# SCH_2022-03-13.net
KiCad netlist of a schematic drawn in Altium Designer
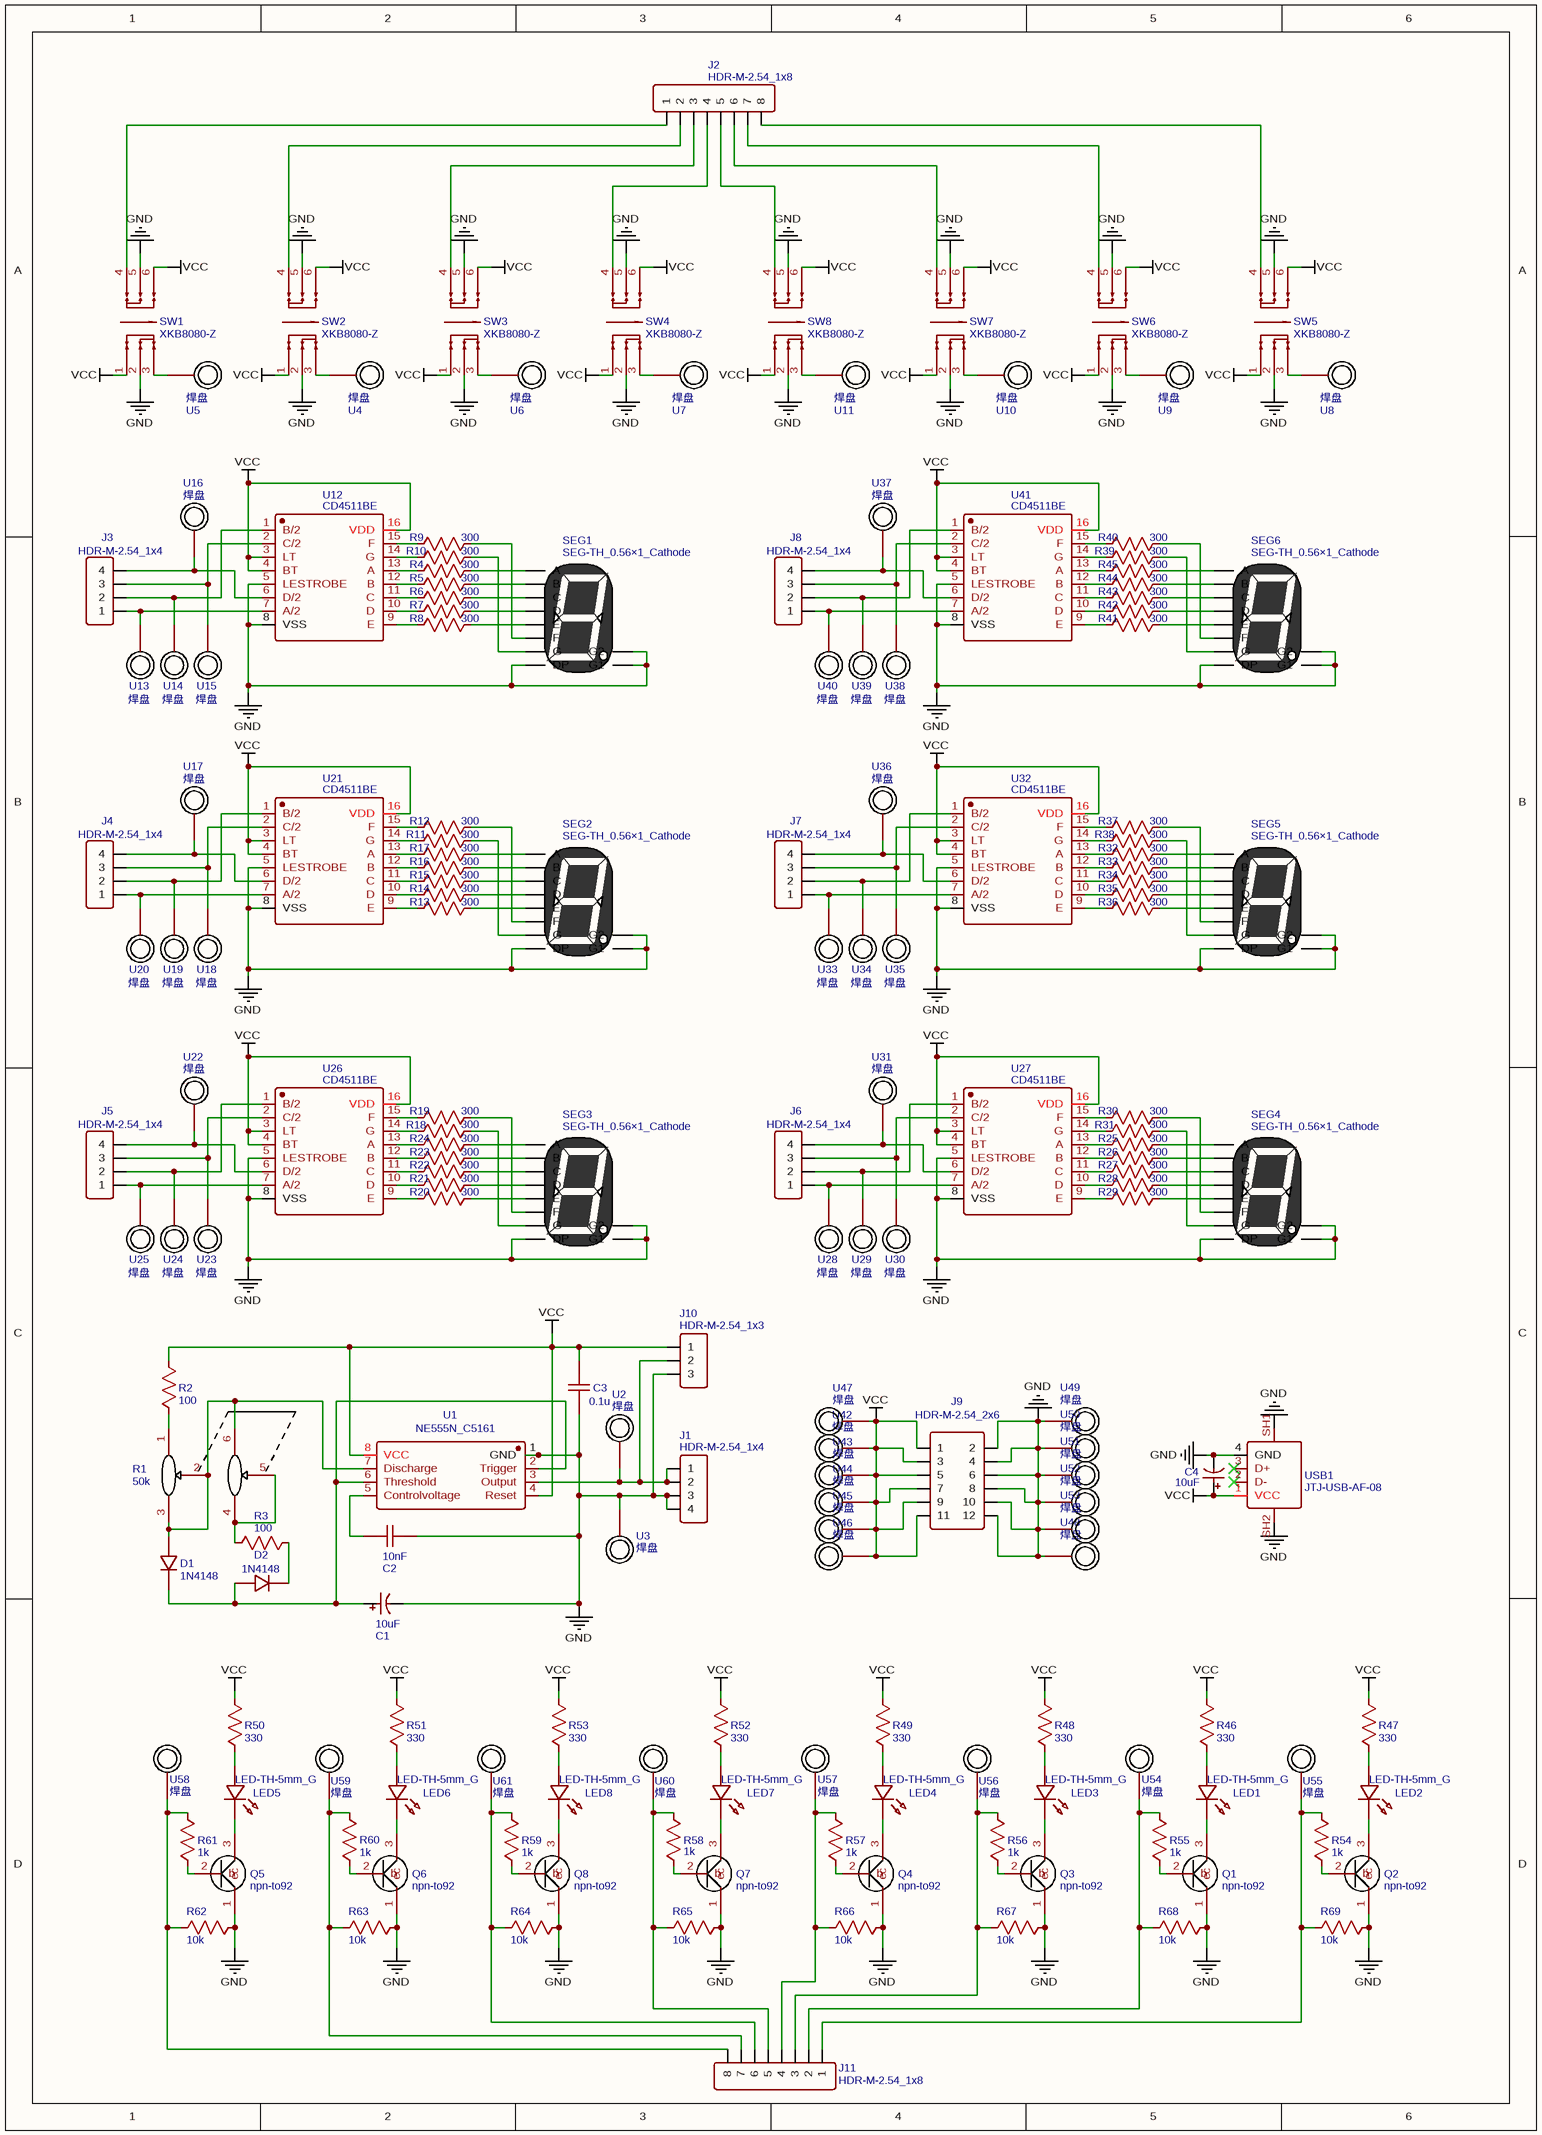
[diagram p0: SCH_2022-03-13.schdoc]

(export (version "E")
  (design (tool "Eeschema 10.0.6"))
  (components
    (comp (ref "C1")
      (value "10uF")
      (footprint "CAP-TH_BD1.0-P2.54-D6.3-FD")
      (fields
        (field (name "BOM_SUPPLIER PART") "C45076")
        (field (name "BOM_MANUFACTURER PART") "100uF 35V 6.3*11")
      )
      (libsource (lib "altium-import") (part "root_0_10uF_"))
    )
    (comp (ref "C2")
      (value "10nF")
      (footprint "RAD-0.2")
      (fields (field (name "CONTRIBUTOR") "LCEDA_Lib"))
      (libsource (lib "altium-import") (part "root_2_10nF_"))
    )
    (comp (ref "C3")
      (value "0.1u")
      (footprint "RAD-0.2")
      (fields (field (name "CONTRIBUTOR") "LCEDA_Lib"))
      (libsource (lib "altium-import") (part "root_1_0.1u_"))
    )
    (comp (ref "C4")
      (value "10uF")
      (footprint "CAP-TH_BD1.0-P2.54-D6.3-FD")
      (fields
        (field (name "BOM_SUPPLIER PART") "C45076")
        (field (name "BOM_MANUFACTURER PART") "100uF 35V 6.3*11")
      )
      (libsource (lib "altium-import") (part "root_1_10uF_"))
    )
    (comp (ref "D1")
      (value "1N4148")
      (footprint "DO-35_BD2.0-L4.2-P8.20-D0.5-RD")
      (fields (field (name "BOM_SUPPLIER PART") "C13769") (field (name "CONTRIBUTOR") "LCSC"))
      (libsource (lib "altium-import") (part "root_1_1N4148_"))
    )
    (comp (ref "D2")
      (value "1N4148")
      (footprint "DO-35_BD2.0-L4.2-P8.20-D0.5-RD")
      (fields (field (name "BOM_SUPPLIER PART") "C13769") (field (name "CONTRIBUTOR") "LCSC"))
      (libsource (lib "altium-import") (part "root_2_1N4148_"))
    )
    (comp (ref "J1")
      (value "HDR-M-2.54_1x4")
      (footprint "HDR-M-2.54_1X4")
      (fields (field (name "BOM_SUPPLIER PART") "C124378") (field (name "CONTRIBUTOR") "LCEDA_Lib"))
      (libsource (lib "altium-import") (part "root_0_HDR-M-2.54_1x4_"))
    )
    (comp (ref "J2")
      (value "HDR-M-2.54_1x8")
      (footprint "HDR-M-2.54_1X8")
      (fields (field (name "BOM_SUPPLIER PART") "C190820") (field (name "CONTRIBUTOR") "LCEDA_Lib"))
      (libsource (lib "altium-import") (part "root_1_HDR-M-2.54_1x8_"))
    )
    (comp (ref "J3")
      (value "HDR-M-2.54_1x4")
      (footprint "HDR-M-2.54_1X4")
      (fields (field (name "BOM_SUPPLIER PART") "C124378") (field (name "CONTRIBUTOR") "LCEDA_Lib"))
      (libsource (lib "altium-import") (part "root_2_HDR-M-2.54_1x4_"))
    )
    (comp (ref "J4")
      (value "HDR-M-2.54_1x4")
      (footprint "HDR-M-2.54_1X4")
      (fields (field (name "BOM_SUPPLIER PART") "C124378") (field (name "CONTRIBUTOR") "LCEDA_Lib"))
      (libsource (lib "altium-import") (part "root_2_HDR-M-2.54_1x4_"))
    )
    (comp (ref "J5")
      (value "HDR-M-2.54_1x4")
      (footprint "HDR-M-2.54_1X4")
      (fields (field (name "BOM_SUPPLIER PART") "C124378") (field (name "CONTRIBUTOR") "LCEDA_Lib"))
      (libsource (lib "altium-import") (part "root_2_HDR-M-2.54_1x4_"))
    )
    (comp (ref "J6")
      (value "HDR-M-2.54_1x4")
      (footprint "HDR-M-2.54_1X4")
      (fields (field (name "BOM_SUPPLIER PART") "C124378") (field (name "CONTRIBUTOR") "LCEDA_Lib"))
      (libsource (lib "altium-import") (part "root_2_HDR-M-2.54_1x4_"))
    )
    (comp (ref "J7")
      (value "HDR-M-2.54_1x4")
      (footprint "HDR-M-2.54_1X4")
      (fields (field (name "BOM_SUPPLIER PART") "C124378") (field (name "CONTRIBUTOR") "LCEDA_Lib"))
      (libsource (lib "altium-import") (part "root_2_HDR-M-2.54_1x4_"))
    )
    (comp (ref "J8")
      (value "HDR-M-2.54_1x4")
      (footprint "HDR-M-2.54_1X4")
      (fields (field (name "BOM_SUPPLIER PART") "C124378") (field (name "CONTRIBUTOR") "LCEDA_Lib"))
      (libsource (lib "altium-import") (part "root_2_HDR-M-2.54_1x4_"))
    )
    (comp (ref "J9")
      (value "HDR-M-2.54_2x6")
      (footprint "HDR-M-2.54_2X6")
      (fields (field (name "BOM_SUPPLIER PART") "C124388") (field (name "CONTRIBUTOR") "LCEDA_Lib"))
      (libsource (lib "altium-import") (part "root_0_HDR-M-2.54_2x6_"))
    )
    (comp (ref "J10")
      (value "HDR-M-2.54_1x3")
      (footprint "HDR-M-2.54_1X3")
      (fields (field (name "BOM_SUPPLIER PART") "C180248") (field (name "CONTRIBUTOR") "LCEDA_Lib"))
      (libsource (lib "altium-import") (part "root_0_HDR-M-2.54_1x3_"))
    )
    (comp (ref "J11")
      (value "HDR-M-2.54_1x8")
      (footprint "HDR-M-2.54_1X8")
      (fields (field (name "BOM_SUPPLIER PART") "C190820") (field (name "CONTRIBUTOR") "LCEDA_Lib"))
      (libsource (lib "altium-import") (part "root_3_HDR-M-2.54_1x8_"))
    )
    (comp (ref "LED1")
      (value "LED-TH-5mm_G")
      (footprint "LED-TH_BD5.0_GREEN")
      (fields
        (field (name "BOM_MANUFACTURER PART") "333-2SYGD/S530-E2")
        (field (name "BOM_SUPPLIER PART") "C88163")
        (field (name "CONTRIBUTOR") "LCEDA_Lib")
      )
      (libsource (lib "altium-import") (part "root_3_LED-TH-5mm_G_"))
    )
    (comp (ref "LED2")
      (value "LED-TH-5mm_G")
      (footprint "LED-TH_BD5.0_GREEN")
      (fields
        (field (name "BOM_MANUFACTURER PART") "333-2SYGD/S530-E2")
        (field (name "BOM_SUPPLIER PART") "C88163")
        (field (name "CONTRIBUTOR") "LCEDA_Lib")
      )
      (libsource (lib "altium-import") (part "root_3_LED-TH-5mm_G_"))
    )
    (comp (ref "LED3")
      (value "LED-TH-5mm_G")
      (footprint "LED-TH_BD5.0_GREEN")
      (fields
        (field (name "BOM_MANUFACTURER PART") "333-2SYGD/S530-E2")
        (field (name "BOM_SUPPLIER PART") "C88163")
        (field (name "CONTRIBUTOR") "LCEDA_Lib")
      )
      (libsource (lib "altium-import") (part "root_3_LED-TH-5mm_G_"))
    )
    (comp (ref "LED4")
      (value "LED-TH-5mm_G")
      (footprint "LED-TH_BD5.0_GREEN")
      (fields
        (field (name "BOM_MANUFACTURER PART") "333-2SYGD/S530-E2")
        (field (name "BOM_SUPPLIER PART") "C88163")
        (field (name "CONTRIBUTOR") "LCEDA_Lib")
      )
      (libsource (lib "altium-import") (part "root_3_LED-TH-5mm_G_"))
    )
    (comp (ref "LED5")
      (value "LED-TH-5mm_G")
      (footprint "LED-TH_BD5.0_GREEN")
      (fields
        (field (name "BOM_MANUFACTURER PART") "333-2SYGD/S530-E2")
        (field (name "BOM_SUPPLIER PART") "C88163")
        (field (name "CONTRIBUTOR") "LCEDA_Lib")
      )
      (libsource (lib "altium-import") (part "root_3_LED-TH-5mm_G_"))
    )
    (comp (ref "LED6")
      (value "LED-TH-5mm_G")
      (footprint "LED-TH_BD5.0_GREEN")
      (fields
        (field (name "BOM_MANUFACTURER PART") "333-2SYGD/S530-E2")
        (field (name "BOM_SUPPLIER PART") "C88163")
        (field (name "CONTRIBUTOR") "LCEDA_Lib")
      )
      (libsource (lib "altium-import") (part "root_3_LED-TH-5mm_G_"))
    )
    (comp (ref "LED7")
      (value "LED-TH-5mm_G")
      (footprint "LED-TH_BD5.0_GREEN")
      (fields
        (field (name "BOM_MANUFACTURER PART") "333-2SYGD/S530-E2")
        (field (name "BOM_SUPPLIER PART") "C88163")
        (field (name "CONTRIBUTOR") "LCEDA_Lib")
      )
      (libsource (lib "altium-import") (part "root_3_LED-TH-5mm_G_"))
    )
    (comp (ref "LED8")
      (value "LED-TH-5mm_G")
      (footprint "LED-TH_BD5.0_GREEN")
      (fields
        (field (name "BOM_MANUFACTURER PART") "333-2SYGD/S530-E2")
        (field (name "BOM_SUPPLIER PART") "C88163")
        (field (name "CONTRIBUTOR") "LCEDA_Lib")
      )
      (libsource (lib "altium-import") (part "root_3_LED-TH-5mm_G_"))
    )
    (comp (ref "Q1")
      (value "npn-to92")
      (footprint "NPN——TO92")
      (fields (field (name "CONTRIBUTOR") "zdy123"))
      (libsource (lib "altium-import") (part "root_0_npn-to92_"))
    )
    (comp (ref "Q2")
      (value "npn-to92")
      (footprint "NPN——TO92")
      (fields (field (name "CONTRIBUTOR") "zdy123"))
      (libsource (lib "altium-import") (part "root_0_npn-to92_"))
    )
    (comp (ref "Q3")
      (value "npn-to92")
      (footprint "NPN——TO92")
      (fields (field (name "CONTRIBUTOR") "zdy123"))
      (libsource (lib "altium-import") (part "root_0_npn-to92_"))
    )
    (comp (ref "Q4")
      (value "npn-to92")
      (footprint "NPN——TO92")
      (fields (field (name "CONTRIBUTOR") "zdy123"))
      (libsource (lib "altium-import") (part "root_0_npn-to92_"))
    )
    (comp (ref "Q5")
      (value "npn-to92")
      (footprint "NPN——TO92")
      (fields (field (name "CONTRIBUTOR") "zdy123"))
      (libsource (lib "altium-import") (part "root_0_npn-to92_"))
    )
    (comp (ref "Q6")
      (value "npn-to92")
      (footprint "NPN——TO92")
      (fields (field (name "CONTRIBUTOR") "zdy123"))
      (libsource (lib "altium-import") (part "root_0_npn-to92_"))
    )
    (comp (ref "Q7")
      (value "npn-to92")
      (footprint "NPN——TO92")
      (fields (field (name "CONTRIBUTOR") "zdy123"))
      (libsource (lib "altium-import") (part "root_0_npn-to92_"))
    )
    (comp (ref "Q8")
      (value "npn-to92")
      (footprint "NPN——TO92")
      (fields (field (name "CONTRIBUTOR") "zdy123"))
      (libsource (lib "altium-import") (part "root_0_npn-to92_"))
    )
    (comp (ref "R1")
      (value "50k")
      (footprint "WH148双联电位器")
      (fields (field (name "CONTRIBUTOR") "lixiansen23333"))
      (libsource (lib "altium-import") (part "root_0_50k_"))
    )
    (comp (ref "R2")
      (value "100")
      (footprint "R_AXIAL-0.4")
      (fields (field (name "CONTRIBUTOR") "LCEDA_Lib"))
      (libsource (lib "altium-import") (part "root_1_100_"))
    )
    (comp (ref "R3")
      (value "100")
      (footprint "R_AXIAL-0.4")
      (fields (field (name "CONTRIBUTOR") "LCEDA_Lib"))
      (libsource (lib "altium-import") (part "root_0_100_"))
    )
    (comp (ref "R4")
      (value "300")
      (footprint "R_AXIAL-0.4")
      (fields (field (name "CONTRIBUTOR") "LCEDA_Lib"))
      (libsource (lib "altium-import") (part "root_0_300_"))
    )
    (comp (ref "R5")
      (value "300")
      (footprint "R_AXIAL-0.4")
      (fields (field (name "CONTRIBUTOR") "LCEDA_Lib"))
      (libsource (lib "altium-import") (part "root_0_300_"))
    )
    (comp (ref "R6")
      (value "300")
      (footprint "R_AXIAL-0.4")
      (fields (field (name "CONTRIBUTOR") "LCEDA_Lib"))
      (libsource (lib "altium-import") (part "root_0_300_"))
    )
    (comp (ref "R7")
      (value "300")
      (footprint "R_AXIAL-0.4")
      (fields (field (name "CONTRIBUTOR") "LCEDA_Lib"))
      (libsource (lib "altium-import") (part "root_0_300_"))
    )
    (comp (ref "R8")
      (value "300")
      (footprint "R_AXIAL-0.4")
      (fields (field (name "CONTRIBUTOR") "LCEDA_Lib"))
      (libsource (lib "altium-import") (part "root_0_300_"))
    )
    (comp (ref "R9")
      (value "300")
      (footprint "R_AXIAL-0.4")
      (fields (field (name "CONTRIBUTOR") "LCEDA_Lib"))
      (libsource (lib "altium-import") (part "root_0_300_"))
    )
    (comp (ref "R10")
      (value "300")
      (footprint "R_AXIAL-0.4")
      (fields (field (name "CONTRIBUTOR") "LCEDA_Lib"))
      (libsource (lib "altium-import") (part "root_0_300_"))
    )
    (comp (ref "R11")
      (value "300")
      (footprint "R_AXIAL-0.4")
      (fields (field (name "CONTRIBUTOR") "LCEDA_Lib"))
      (libsource (lib "altium-import") (part "root_0_300_"))
    )
    (comp (ref "R12")
      (value "300")
      (footprint "R_AXIAL-0.4")
      (fields (field (name "CONTRIBUTOR") "LCEDA_Lib"))
      (libsource (lib "altium-import") (part "root_0_300_"))
    )
    (comp (ref "R13")
      (value "300")
      (footprint "R_AXIAL-0.4")
      (fields (field (name "CONTRIBUTOR") "LCEDA_Lib"))
      (libsource (lib "altium-import") (part "root_0_300_"))
    )
    (comp (ref "R14")
      (value "300")
      (footprint "R_AXIAL-0.4")
      (fields (field (name "CONTRIBUTOR") "LCEDA_Lib"))
      (libsource (lib "altium-import") (part "root_0_300_"))
    )
    (comp (ref "R15")
      (value "300")
      (footprint "R_AXIAL-0.4")
      (fields (field (name "CONTRIBUTOR") "LCEDA_Lib"))
      (libsource (lib "altium-import") (part "root_0_300_"))
    )
    (comp (ref "R16")
      (value "300")
      (footprint "R_AXIAL-0.4")
      (fields (field (name "CONTRIBUTOR") "LCEDA_Lib"))
      (libsource (lib "altium-import") (part "root_0_300_"))
    )
    (comp (ref "R17")
      (value "300")
      (footprint "R_AXIAL-0.4")
      (fields (field (name "CONTRIBUTOR") "LCEDA_Lib"))
      (libsource (lib "altium-import") (part "root_0_300_"))
    )
    (comp (ref "R18")
      (value "300")
      (footprint "R_AXIAL-0.4")
      (fields (field (name "CONTRIBUTOR") "LCEDA_Lib"))
      (libsource (lib "altium-import") (part "root_0_300_"))
    )
    (comp (ref "R19")
      (value "300")
      (footprint "R_AXIAL-0.4")
      (fields (field (name "CONTRIBUTOR") "LCEDA_Lib"))
      (libsource (lib "altium-import") (part "root_0_300_"))
    )
    (comp (ref "R20")
      (value "300")
      (footprint "R_AXIAL-0.4")
      (fields (field (name "CONTRIBUTOR") "LCEDA_Lib"))
      (libsource (lib "altium-import") (part "root_0_300_"))
    )
    (comp (ref "R21")
      (value "300")
      (footprint "R_AXIAL-0.4")
      (fields (field (name "CONTRIBUTOR") "LCEDA_Lib"))
      (libsource (lib "altium-import") (part "root_0_300_"))
    )
    (comp (ref "R22")
      (value "300")
      (footprint "R_AXIAL-0.4")
      (fields (field (name "CONTRIBUTOR") "LCEDA_Lib"))
      (libsource (lib "altium-import") (part "root_0_300_"))
    )
    (comp (ref "R23")
      (value "300")
      (footprint "R_AXIAL-0.4")
      (fields (field (name "CONTRIBUTOR") "LCEDA_Lib"))
      (libsource (lib "altium-import") (part "root_0_300_"))
    )
    (comp (ref "R24")
      (value "300")
      (footprint "R_AXIAL-0.4")
      (fields (field (name "CONTRIBUTOR") "LCEDA_Lib"))
      (libsource (lib "altium-import") (part "root_0_300_"))
    )
    (comp (ref "R25")
      (value "300")
      (footprint "R_AXIAL-0.4")
      (fields (field (name "CONTRIBUTOR") "LCEDA_Lib"))
      (libsource (lib "altium-import") (part "root_0_300_"))
    )
    (comp (ref "R26")
      (value "300")
      (footprint "R_AXIAL-0.4")
      (fields (field (name "CONTRIBUTOR") "LCEDA_Lib"))
      (libsource (lib "altium-import") (part "root_0_300_"))
    )
    (comp (ref "R27")
      (value "300")
      (footprint "R_AXIAL-0.4")
      (fields (field (name "CONTRIBUTOR") "LCEDA_Lib"))
      (libsource (lib "altium-import") (part "root_0_300_"))
    )
    (comp (ref "R28")
      (value "300")
      (footprint "R_AXIAL-0.4")
      (fields (field (name "CONTRIBUTOR") "LCEDA_Lib"))
      (libsource (lib "altium-import") (part "root_0_300_"))
    )
    (comp (ref "R29")
      (value "300")
      (footprint "R_AXIAL-0.4")
      (fields (field (name "CONTRIBUTOR") "LCEDA_Lib"))
      (libsource (lib "altium-import") (part "root_0_300_"))
    )
    (comp (ref "R30")
      (value "300")
      (footprint "R_AXIAL-0.4")
      (fields (field (name "CONTRIBUTOR") "LCEDA_Lib"))
      (libsource (lib "altium-import") (part "root_0_300_"))
    )
    (comp (ref "R31")
      (value "300")
      (footprint "R_AXIAL-0.4")
      (fields (field (name "CONTRIBUTOR") "LCEDA_Lib"))
      (libsource (lib "altium-import") (part "root_0_300_"))
    )
    (comp (ref "R32")
      (value "300")
      (footprint "R_AXIAL-0.4")
      (fields (field (name "CONTRIBUTOR") "LCEDA_Lib"))
      (libsource (lib "altium-import") (part "root_0_300_"))
    )
    (comp (ref "R33")
      (value "300")
      (footprint "R_AXIAL-0.4")
      (fields (field (name "CONTRIBUTOR") "LCEDA_Lib"))
      (libsource (lib "altium-import") (part "root_0_300_"))
    )
    (comp (ref "R34")
      (value "300")
      (footprint "R_AXIAL-0.4")
      (fields (field (name "CONTRIBUTOR") "LCEDA_Lib"))
      (libsource (lib "altium-import") (part "root_0_300_"))
    )
    (comp (ref "R35")
      (value "300")
      (footprint "R_AXIAL-0.4")
      (fields (field (name "CONTRIBUTOR") "LCEDA_Lib"))
      (libsource (lib "altium-import") (part "root_0_300_"))
    )
    (comp (ref "R36")
      (value "300")
      (footprint "R_AXIAL-0.4")
      (fields (field (name "CONTRIBUTOR") "LCEDA_Lib"))
      (libsource (lib "altium-import") (part "root_0_300_"))
    )
    (comp (ref "R37")
      (value "300")
      (footprint "R_AXIAL-0.4")
      (fields (field (name "CONTRIBUTOR") "LCEDA_Lib"))
      (libsource (lib "altium-import") (part "root_0_300_"))
    )
    (comp (ref "R38")
      (value "300")
      (footprint "R_AXIAL-0.4")
      (fields (field (name "CONTRIBUTOR") "LCEDA_Lib"))
      (libsource (lib "altium-import") (part "root_0_300_"))
    )
    (comp (ref "R39")
      (value "300")
      (footprint "R_AXIAL-0.4")
      (fields (field (name "CONTRIBUTOR") "LCEDA_Lib"))
      (libsource (lib "altium-import") (part "root_0_300_"))
    )
    (comp (ref "R40")
      (value "300")
      (footprint "R_AXIAL-0.4")
      (fields (field (name "CONTRIBUTOR") "LCEDA_Lib"))
      (libsource (lib "altium-import") (part "root_0_300_"))
    )
    (comp (ref "R41")
      (value "300")
      (footprint "R_AXIAL-0.4")
      (fields (field (name "CONTRIBUTOR") "LCEDA_Lib"))
      (libsource (lib "altium-import") (part "root_0_300_"))
    )
    (comp (ref "R42")
      (value "300")
      (footprint "R_AXIAL-0.4")
      (fields (field (name "CONTRIBUTOR") "LCEDA_Lib"))
      (libsource (lib "altium-import") (part "root_0_300_"))
    )
    (comp (ref "R43")
      (value "300")
      (footprint "R_AXIAL-0.4")
      (fields (field (name "CONTRIBUTOR") "LCEDA_Lib"))
      (libsource (lib "altium-import") (part "root_0_300_"))
    )
    (comp (ref "R44")
      (value "300")
      (footprint "R_AXIAL-0.4")
      (fields (field (name "CONTRIBUTOR") "LCEDA_Lib"))
      (libsource (lib "altium-import") (part "root_0_300_"))
    )
    (comp (ref "R45")
      (value "300")
      (footprint "R_AXIAL-0.4")
      (fields (field (name "CONTRIBUTOR") "LCEDA_Lib"))
      (libsource (lib "altium-import") (part "root_0_300_"))
    )
    (comp (ref "R46")
      (value "330")
      (footprint "R_AXIAL-0.4")
      (fields (field (name "CONTRIBUTOR") "LCEDA_Lib"))
      (libsource (lib "altium-import") (part "root_1_330_"))
    )
    (comp (ref "R47")
      (value "330")
      (footprint "R_AXIAL-0.4")
      (fields (field (name "CONTRIBUTOR") "LCEDA_Lib"))
      (libsource (lib "altium-import") (part "root_1_330_"))
    )
    (comp (ref "R48")
      (value "330")
      (footprint "R_AXIAL-0.4")
      (fields (field (name "CONTRIBUTOR") "LCEDA_Lib"))
      (libsource (lib "altium-import") (part "root_1_330_"))
    )
    (comp (ref "R49")
      (value "330")
      (footprint "R_AXIAL-0.4")
      (fields (field (name "CONTRIBUTOR") "LCEDA_Lib"))
      (libsource (lib "altium-import") (part "root_1_330_"))
    )
    (comp (ref "R50")
      (value "330")
      (footprint "R_AXIAL-0.4")
      (fields (field (name "CONTRIBUTOR") "LCEDA_Lib"))
      (libsource (lib "altium-import") (part "root_1_330_"))
    )
    (comp (ref "R51")
      (value "330")
      (footprint "R_AXIAL-0.4")
      (fields (field (name "CONTRIBUTOR") "LCEDA_Lib"))
      (libsource (lib "altium-import") (part "root_1_330_"))
    )
    (comp (ref "R52")
      (value "330")
      (footprint "R_AXIAL-0.4")
      (fields (field (name "CONTRIBUTOR") "LCEDA_Lib"))
      (libsource (lib "altium-import") (part "root_1_330_"))
    )
    (comp (ref "R53")
      (value "330")
      (footprint "R_AXIAL-0.4")
      (fields (field (name "CONTRIBUTOR") "LCEDA_Lib"))
      (libsource (lib "altium-import") (part "root_1_330_"))
    )
    (comp (ref "R54")
      (value "1k")
      (footprint "R_AXIAL-0.4")
      (fields (field (name "CONTRIBUTOR") "LCEDA_Lib"))
      (libsource (lib "altium-import") (part "root_1_2k_"))
    )
    (comp (ref "R55")
      (value "1k")
      (footprint "R_AXIAL-0.4")
      (fields (field (name "CONTRIBUTOR") "LCEDA_Lib"))
      (libsource (lib "altium-import") (part "root_1_2k_"))
    )
    (comp (ref "R56")
      (value "1k")
      (footprint "R_AXIAL-0.4")
      (fields (field (name "CONTRIBUTOR") "LCEDA_Lib"))
      (libsource (lib "altium-import") (part "root_1_2k_"))
    )
    (comp (ref "R57")
      (value "1k")
      (footprint "R_AXIAL-0.4")
      (fields (field (name "CONTRIBUTOR") "LCEDA_Lib"))
      (libsource (lib "altium-import") (part "root_1_2k_"))
    )
    (comp (ref "R58")
      (value "1k")
      (footprint "R_AXIAL-0.4")
      (fields (field (name "CONTRIBUTOR") "LCEDA_Lib"))
      (libsource (lib "altium-import") (part "root_1_2k_"))
    )
    (comp (ref "R59")
      (value "1k")
      (footprint "R_AXIAL-0.4")
      (fields (field (name "CONTRIBUTOR") "LCEDA_Lib"))
      (libsource (lib "altium-import") (part "root_1_2k_"))
    )
    (comp (ref "R60")
      (value "1k")
      (footprint "R_AXIAL-0.4")
      (fields (field (name "CONTRIBUTOR") "LCEDA_Lib"))
      (libsource (lib "altium-import") (part "root_1_2k_"))
    )
    (comp (ref "R61")
      (value "1k")
      (footprint "R_AXIAL-0.4")
      (fields (field (name "CONTRIBUTOR") "LCEDA_Lib"))
      (libsource (lib "altium-import") (part "root_1_2k_"))
    )
    (comp (ref "R62")
      (value "10k")
      (footprint "R_AXIAL-0.4")
      (fields (field (name "CONTRIBUTOR") "LCEDA_Lib"))
      (libsource (lib "altium-import") (part "root_2_2k_"))
    )
    (comp (ref "R63")
      (value "10k")
      (footprint "R_AXIAL-0.4")
      (fields (field (name "CONTRIBUTOR") "LCEDA_Lib"))
      (libsource (lib "altium-import") (part "root_2_2k_"))
    )
    (comp (ref "R64")
      (value "10k")
      (footprint "R_AXIAL-0.4")
      (fields (field (name "CONTRIBUTOR") "LCEDA_Lib"))
      (libsource (lib "altium-import") (part "root_2_2k_"))
    )
    (comp (ref "R65")
      (value "10k")
      (footprint "R_AXIAL-0.4")
      (fields (field (name "CONTRIBUTOR") "LCEDA_Lib"))
      (libsource (lib "altium-import") (part "root_2_2k_"))
    )
    (comp (ref "R66")
      (value "10k")
      (footprint "R_AXIAL-0.4")
      (fields (field (name "CONTRIBUTOR") "LCEDA_Lib"))
      (libsource (lib "altium-import") (part "root_2_2k_"))
    )
    (comp (ref "R67")
      (value "10k")
      (footprint "R_AXIAL-0.4")
      (fields (field (name "CONTRIBUTOR") "LCEDA_Lib"))
      (libsource (lib "altium-import") (part "root_2_2k_"))
    )
    (comp (ref "R68")
      (value "10k")
      (footprint "R_AXIAL-0.4")
      (fields (field (name "CONTRIBUTOR") "LCEDA_Lib"))
      (libsource (lib "altium-import") (part "root_2_2k_"))
    )
    (comp (ref "R69")
      (value "10k")
      (footprint "R_AXIAL-0.4")
      (fields (field (name "CONTRIBUTOR") "LCEDA_Lib"))
      (libsource (lib "altium-import") (part "root_2_2k_"))
    )
    (comp (ref "SEG1")
      (value "SEG-TH_0.56×1_Cathode")
      (footprint "LED-SEG-TH_10P-L12.6-W19.0-P2.54-S15.24-BL")
      (fields (field (name "BOM_SUPPLIER PART") "C8093") (field (name "CONTRIBUTOR") "LCEDA_01"))
      (libsource (lib "altium-import") (part "root_0_SEG-TH_0.56×1_Cathode_"))
    )
    (comp (ref "SEG2")
      (value "SEG-TH_0.56×1_Cathode")
      (footprint "LED-SEG-TH_10P-L12.6-W19.0-P2.54-S15.24-BL")
      (fields (field (name "BOM_SUPPLIER PART") "C8093") (field (name "CONTRIBUTOR") "LCEDA_01"))
      (libsource (lib "altium-import") (part "root_0_SEG-TH_0.56×1_Cathode_"))
    )
    (comp (ref "SEG3")
      (value "SEG-TH_0.56×1_Cathode")
      (footprint "LED-SEG-TH_10P-L12.6-W19.0-P2.54-S15.24-BL")
      (fields (field (name "BOM_SUPPLIER PART") "C8093") (field (name "CONTRIBUTOR") "LCEDA_01"))
      (libsource (lib "altium-import") (part "root_0_SEG-TH_0.56×1_Cathode_"))
    )
    (comp (ref "SEG4")
      (value "SEG-TH_0.56×1_Cathode")
      (footprint "LED-SEG-TH_10P-L12.6-W19.0-P2.54-S15.24-BL")
      (fields (field (name "BOM_SUPPLIER PART") "C8093") (field (name "CONTRIBUTOR") "LCEDA_01"))
      (libsource (lib "altium-import") (part "root_0_SEG-TH_0.56×1_Cathode_"))
    )
    (comp (ref "SEG5")
      (value "SEG-TH_0.56×1_Cathode")
      (footprint "LED-SEG-TH_10P-L12.6-W19.0-P2.54-S15.24-BL")
      (fields (field (name "BOM_SUPPLIER PART") "C8093") (field (name "CONTRIBUTOR") "LCEDA_01"))
      (libsource (lib "altium-import") (part "root_0_SEG-TH_0.56×1_Cathode_"))
    )
    (comp (ref "SEG6")
      (value "SEG-TH_0.56×1_Cathode")
      (footprint "LED-SEG-TH_10P-L12.6-W19.0-P2.54-S15.24-BL")
      (fields (field (name "BOM_SUPPLIER PART") "C8093") (field (name "CONTRIBUTOR") "LCEDA_01"))
      (libsource (lib "altium-import") (part "root_0_SEG-TH_0.56×1_Cathode_"))
    )
    (comp (ref "SW1")
      (value "XKB8080-Z")
      (footprint "SW-TH_6P-L8.0-W8.0-P2.50")
      (fields (field (name "BOM_SUPPLIER PART") "C318860") (field (name "CONTRIBUTOR") "LCSC"))
      (libsource (lib "altium-import") (part "root_0_XKB8080-Z_"))
    )
    (comp (ref "SW2")
      (value "XKB8080-Z")
      (footprint "SW-TH_6P-L8.0-W8.0-P2.50")
      (fields (field (name "BOM_SUPPLIER PART") "C318860") (field (name "CONTRIBUTOR") "LCSC"))
      (libsource (lib "altium-import") (part "root_0_XKB8080-Z_"))
    )
    (comp (ref "SW3")
      (value "XKB8080-Z")
      (footprint "SW-TH_6P-L8.0-W8.0-P2.50")
      (fields (field (name "BOM_SUPPLIER PART") "C318860") (field (name "CONTRIBUTOR") "LCSC"))
      (libsource (lib "altium-import") (part "root_0_XKB8080-Z_"))
    )
    (comp (ref "SW4")
      (value "XKB8080-Z")
      (footprint "SW-TH_6P-L8.0-W8.0-P2.50")
      (fields (field (name "BOM_SUPPLIER PART") "C318860") (field (name "CONTRIBUTOR") "LCSC"))
      (libsource (lib "altium-import") (part "root_0_XKB8080-Z_"))
    )
    (comp (ref "SW5")
      (value "XKB8080-Z")
      (footprint "SW-TH_6P-L8.0-W8.0-P2.50")
      (fields (field (name "BOM_SUPPLIER PART") "C318860") (field (name "CONTRIBUTOR") "LCSC"))
      (libsource (lib "altium-import") (part "root_0_XKB8080-Z_"))
    )
    (comp (ref "SW6")
      (value "XKB8080-Z")
      (footprint "SW-TH_6P-L8.0-W8.0-P2.50")
      (fields (field (name "BOM_SUPPLIER PART") "C318860") (field (name "CONTRIBUTOR") "LCSC"))
      (libsource (lib "altium-import") (part "root_0_XKB8080-Z_"))
    )
    (comp (ref "SW7")
      (value "XKB8080-Z")
      (footprint "SW-TH_6P-L8.0-W8.0-P2.50")
      (fields (field (name "BOM_SUPPLIER PART") "C318860") (field (name "CONTRIBUTOR") "LCSC"))
      (libsource (lib "altium-import") (part "root_0_XKB8080-Z_"))
    )
    (comp (ref "SW8")
      (value "XKB8080-Z")
      (footprint "SW-TH_6P-L8.0-W8.0-P2.50")
      (fields (field (name "BOM_SUPPLIER PART") "C318860") (field (name "CONTRIBUTOR") "LCSC"))
      (libsource (lib "altium-import") (part "root_0_XKB8080-Z_"))
    )
    (comp (ref "U1")
      (value "NE555N_C5161")
      (footprint "DIP-8_L9.7-W6.4-P2.54-LS7.6-BL")
      (fields
        (field (name "BOM_SUPPLIER PART") "C5161")
        (field (name "BOM_MANUFACTURER PART") "NE555N")
        (field (name "CONTRIBUTOR") "LCSC")
      )
      (libsource (lib "altium-import") (part "root_0_NE555N_C5161_"))
    )
    (comp (ref "U2")
      (value "焊盘")
      (footprint "6*4焊盘")
      (fields (field (name "CONTRIBUTOR") "dhx233"))
      (libsource (lib "altium-import") (part "root_0_焊盘_"))
    )
    (comp (ref "U3")
      (value "焊盘")
      (footprint "6*4焊盘")
      (fields (field (name "CONTRIBUTOR") "dhx233"))
      (libsource (lib "altium-import") (part "root_2_焊盘_"))
    )
    (comp (ref "U4")
      (value "焊盘")
      (footprint "6*4焊盘")
      (fields (field (name "CONTRIBUTOR") "dhx233"))
      (libsource (lib "altium-import") (part "root_3_焊盘_"))
    )
    (comp (ref "U5")
      (value "焊盘")
      (footprint "6*4焊盘")
      (fields (field (name "CONTRIBUTOR") "dhx233"))
      (libsource (lib "altium-import") (part "root_3_焊盘_"))
    )
    (comp (ref "U6")
      (value "焊盘")
      (footprint "6*4焊盘")
      (fields (field (name "CONTRIBUTOR") "dhx233"))
      (libsource (lib "altium-import") (part "root_3_焊盘_"))
    )
    (comp (ref "U7")
      (value "焊盘")
      (footprint "6*4焊盘")
      (fields (field (name "CONTRIBUTOR") "dhx233"))
      (libsource (lib "altium-import") (part "root_3_焊盘_"))
    )
    (comp (ref "U8")
      (value "焊盘")
      (footprint "6*4焊盘")
      (fields (field (name "CONTRIBUTOR") "dhx233"))
      (libsource (lib "altium-import") (part "root_3_焊盘_"))
    )
    (comp (ref "U9")
      (value "焊盘")
      (footprint "6*4焊盘")
      (fields (field (name "CONTRIBUTOR") "dhx233"))
      (libsource (lib "altium-import") (part "root_3_焊盘_"))
    )
    (comp (ref "U10")
      (value "焊盘")
      (footprint "6*4焊盘")
      (fields (field (name "CONTRIBUTOR") "dhx233"))
      (libsource (lib "altium-import") (part "root_3_焊盘_"))
    )
    (comp (ref "U11")
      (value "焊盘")
      (footprint "6*4焊盘")
      (fields (field (name "CONTRIBUTOR") "dhx233"))
      (libsource (lib "altium-import") (part "root_3_焊盘_"))
    )
    (comp (ref "U12")
      (value "CD4511BE")
      (footprint "DIP-16_L19.8-W6.5-P2.54-LS7.6-BL")
      (fields (field (name "BOM_SUPPLIER PART") "C5327"))
      (libsource (lib "altium-import") (part "root_0_CD4511BE_"))
    )
    (comp (ref "U13")
      (value "焊盘")
      (footprint "6*4焊盘")
      (fields (field (name "CONTRIBUTOR") "dhx233"))
      (libsource (lib "altium-import") (part "root_2_焊盘_"))
    )
    (comp (ref "U14")
      (value "焊盘")
      (footprint "6*4焊盘")
      (fields (field (name "CONTRIBUTOR") "dhx233"))
      (libsource (lib "altium-import") (part "root_2_焊盘_"))
    )
    (comp (ref "U15")
      (value "焊盘")
      (footprint "6*4焊盘")
      (fields (field (name "CONTRIBUTOR") "dhx233"))
      (libsource (lib "altium-import") (part "root_2_焊盘_"))
    )
    (comp (ref "U16")
      (value "焊盘")
      (footprint "6*4焊盘")
      (fields (field (name "CONTRIBUTOR") "dhx233"))
      (libsource (lib "altium-import") (part "root_0_焊盘_"))
    )
    (comp (ref "U17")
      (value "焊盘")
      (footprint "6*4焊盘")
      (fields (field (name "CONTRIBUTOR") "dhx233"))
      (libsource (lib "altium-import") (part "root_0_焊盘_"))
    )
    (comp (ref "U18")
      (value "焊盘")
      (footprint "6*4焊盘")
      (fields (field (name "CONTRIBUTOR") "dhx233"))
      (libsource (lib "altium-import") (part "root_2_焊盘_"))
    )
    (comp (ref "U19")
      (value "焊盘")
      (footprint "6*4焊盘")
      (fields (field (name "CONTRIBUTOR") "dhx233"))
      (libsource (lib "altium-import") (part "root_2_焊盘_"))
    )
    (comp (ref "U20")
      (value "焊盘")
      (footprint "6*4焊盘")
      (fields (field (name "CONTRIBUTOR") "dhx233"))
      (libsource (lib "altium-import") (part "root_2_焊盘_"))
    )
    (comp (ref "U21")
      (value "CD4511BE")
      (footprint "DIP-16_L19.8-W6.5-P2.54-LS7.6-BL")
      (fields (field (name "BOM_SUPPLIER PART") "C5327"))
      (libsource (lib "altium-import") (part "root_0_CD4511BE_"))
    )
    (comp (ref "U22")
      (value "焊盘")
      (footprint "6*4焊盘")
      (fields (field (name "CONTRIBUTOR") "dhx233"))
      (libsource (lib "altium-import") (part "root_0_焊盘_"))
    )
    (comp (ref "U23")
      (value "焊盘")
      (footprint "6*4焊盘")
      (fields (field (name "CONTRIBUTOR") "dhx233"))
      (libsource (lib "altium-import") (part "root_2_焊盘_"))
    )
    (comp (ref "U24")
      (value "焊盘")
      (footprint "6*4焊盘")
      (fields (field (name "CONTRIBUTOR") "dhx233"))
      (libsource (lib "altium-import") (part "root_2_焊盘_"))
    )
    (comp (ref "U25")
      (value "焊盘")
      (footprint "6*4焊盘")
      (fields (field (name "CONTRIBUTOR") "dhx233"))
      (libsource (lib "altium-import") (part "root_2_焊盘_"))
    )
    (comp (ref "U26")
      (value "CD4511BE")
      (footprint "DIP-16_L19.8-W6.5-P2.54-LS7.6-BL")
      (fields (field (name "BOM_SUPPLIER PART") "C5327"))
      (libsource (lib "altium-import") (part "root_0_CD4511BE_"))
    )
    (comp (ref "U27")
      (value "CD4511BE")
      (footprint "DIP-16_L19.8-W6.5-P2.54-LS7.6-BL")
      (fields (field (name "BOM_SUPPLIER PART") "C5327"))
      (libsource (lib "altium-import") (part "root_0_CD4511BE_"))
    )
    (comp (ref "U28")
      (value "焊盘")
      (footprint "6*4焊盘")
      (fields (field (name "CONTRIBUTOR") "dhx233"))
      (libsource (lib "altium-import") (part "root_2_焊盘_"))
    )
    (comp (ref "U29")
      (value "焊盘")
      (footprint "6*4焊盘")
      (fields (field (name "CONTRIBUTOR") "dhx233"))
      (libsource (lib "altium-import") (part "root_2_焊盘_"))
    )
    (comp (ref "U30")
      (value "焊盘")
      (footprint "6*4焊盘")
      (fields (field (name "CONTRIBUTOR") "dhx233"))
      (libsource (lib "altium-import") (part "root_2_焊盘_"))
    )
    (comp (ref "U31")
      (value "焊盘")
      (footprint "6*4焊盘")
      (fields (field (name "CONTRIBUTOR") "dhx233"))
      (libsource (lib "altium-import") (part "root_0_焊盘_"))
    )
    (comp (ref "U32")
      (value "CD4511BE")
      (footprint "DIP-16_L19.8-W6.5-P2.54-LS7.6-BL")
      (fields (field (name "BOM_SUPPLIER PART") "C5327"))
      (libsource (lib "altium-import") (part "root_0_CD4511BE_"))
    )
    (comp (ref "U33")
      (value "焊盘")
      (footprint "6*4焊盘")
      (fields (field (name "CONTRIBUTOR") "dhx233"))
      (libsource (lib "altium-import") (part "root_2_焊盘_"))
    )
    (comp (ref "U34")
      (value "焊盘")
      (footprint "6*4焊盘")
      (fields (field (name "CONTRIBUTOR") "dhx233"))
      (libsource (lib "altium-import") (part "root_2_焊盘_"))
    )
    (comp (ref "U35")
      (value "焊盘")
      (footprint "6*4焊盘")
      (fields (field (name "CONTRIBUTOR") "dhx233"))
      (libsource (lib "altium-import") (part "root_2_焊盘_"))
    )
    (comp (ref "U36")
      (value "焊盘")
      (footprint "6*4焊盘")
      (fields (field (name "CONTRIBUTOR") "dhx233"))
      (libsource (lib "altium-import") (part "root_0_焊盘_"))
    )
    (comp (ref "U37")
      (value "焊盘")
      (footprint "6*4焊盘")
      (fields (field (name "CONTRIBUTOR") "dhx233"))
      (libsource (lib "altium-import") (part "root_0_焊盘_"))
    )
    (comp (ref "U38")
      (value "焊盘")
      (footprint "6*4焊盘")
      (fields (field (name "CONTRIBUTOR") "dhx233"))
      (libsource (lib "altium-import") (part "root_2_焊盘_"))
    )
    (comp (ref "U39")
      (value "焊盘")
      (footprint "6*4焊盘")
      (fields (field (name "CONTRIBUTOR") "dhx233"))
      (libsource (lib "altium-import") (part "root_2_焊盘_"))
    )
    (comp (ref "U40")
      (value "焊盘")
      (footprint "6*4焊盘")
      (fields (field (name "CONTRIBUTOR") "dhx233"))
      (libsource (lib "altium-import") (part "root_2_焊盘_"))
    )
    (comp (ref "U41")
      (value "CD4511BE")
      (footprint "DIP-16_L19.8-W6.5-P2.54-LS7.6-BL")
      (fields (field (name "BOM_SUPPLIER PART") "C5327"))
      (libsource (lib "altium-import") (part "root_0_CD4511BE_"))
    )
    (comp (ref "U42")
      (value "焊盘")
      (footprint "6*4焊盘")
      (fields (field (name "CONTRIBUTOR") "dhx233"))
      (libsource (lib "altium-import") (part "root_1_焊盘_"))
    )
    (comp (ref "U43")
      (value "焊盘")
      (footprint "6*4焊盘")
      (fields (field (name "CONTRIBUTOR") "dhx233"))
      (libsource (lib "altium-import") (part "root_1_焊盘_"))
    )
    (comp (ref "U44")
      (value "焊盘")
      (footprint "6*4焊盘")
      (fields (field (name "CONTRIBUTOR") "dhx233"))
      (libsource (lib "altium-import") (part "root_1_焊盘_"))
    )
    (comp (ref "U45")
      (value "焊盘")
      (footprint "6*4焊盘")
      (fields (field (name "CONTRIBUTOR") "dhx233"))
      (libsource (lib "altium-import") (part "root_1_焊盘_"))
    )
    (comp (ref "U46")
      (value "焊盘")
      (footprint "6*4焊盘")
      (fields (field (name "CONTRIBUTOR") "dhx233"))
      (libsource (lib "altium-import") (part "root_1_焊盘_"))
    )
    (comp (ref "U47")
      (value "焊盘")
      (footprint "6*4焊盘")
      (fields (field (name "CONTRIBUTOR") "dhx233"))
      (libsource (lib "altium-import") (part "root_1_焊盘_"))
    )
    (comp (ref "U48")
      (value "焊盘")
      (footprint "6*4焊盘")
      (fields (field (name "CONTRIBUTOR") "dhx233"))
      (libsource (lib "") (part "root_3_焊盘__1"))
    )
    (comp (ref "U49")
      (value "焊盘")
      (footprint "6*4焊盘")
      (fields (field (name "CONTRIBUTOR") "dhx233"))
      (libsource (lib "") (part "root_3_焊盘__1"))
    )
    (comp (ref "U50")
      (value "焊盘")
      (footprint "6*4焊盘")
      (fields (field (name "CONTRIBUTOR") "dhx233"))
      (libsource (lib "") (part "root_3_焊盘__1"))
    )
    (comp (ref "U51")
      (value "焊盘")
      (footprint "6*4焊盘")
      (fields (field (name "CONTRIBUTOR") "dhx233"))
      (libsource (lib "") (part "root_3_焊盘__1"))
    )
    (comp (ref "U52")
      (value "焊盘")
      (footprint "6*4焊盘")
      (fields (field (name "CONTRIBUTOR") "dhx233"))
      (libsource (lib "") (part "root_3_焊盘__1"))
    )
    (comp (ref "U53")
      (value "焊盘")
      (footprint "6*4焊盘")
      (fields (field (name "CONTRIBUTOR") "dhx233"))
      (libsource (lib "") (part "root_3_焊盘__1"))
    )
    (comp (ref "U54")
      (value "焊盘")
      (footprint "6*4焊盘")
      (fields (field (name "CONTRIBUTOR") "dhx233"))
      (libsource (lib "altium-import") (part "root_0_焊盘_"))
    )
    (comp (ref "U55")
      (value "焊盘")
      (footprint "6*4焊盘")
      (fields (field (name "CONTRIBUTOR") "dhx233"))
      (libsource (lib "altium-import") (part "root_0_焊盘_"))
    )
    (comp (ref "U56")
      (value "焊盘")
      (footprint "6*4焊盘")
      (fields (field (name "CONTRIBUTOR") "dhx233"))
      (libsource (lib "altium-import") (part "root_0_焊盘_"))
    )
    (comp (ref "U57")
      (value "焊盘")
      (footprint "6*4焊盘")
      (fields (field (name "CONTRIBUTOR") "dhx233"))
      (libsource (lib "altium-import") (part "root_0_焊盘_"))
    )
    (comp (ref "U58")
      (value "焊盘")
      (footprint "6*4焊盘")
      (fields (field (name "CONTRIBUTOR") "dhx233"))
      (libsource (lib "altium-import") (part "root_0_焊盘_"))
    )
    (comp (ref "U59")
      (value "焊盘")
      (footprint "6*4焊盘")
      (fields (field (name "CONTRIBUTOR") "dhx233"))
      (libsource (lib "altium-import") (part "root_0_焊盘_"))
    )
    (comp (ref "U60")
      (value "焊盘")
      (footprint "6*4焊盘")
      (fields (field (name "CONTRIBUTOR") "dhx233"))
      (libsource (lib "altium-import") (part "root_0_焊盘_"))
    )
    (comp (ref "U61")
      (value "焊盘")
      (footprint "6*4焊盘")
      (fields (field (name "CONTRIBUTOR") "dhx233"))
      (libsource (lib "altium-import") (part "root_0_焊盘_"))
    )
    (comp (ref "USB1")
      (value "JTJ-USB-AF-08")
      (footprint "USB-A-TH__USB-AF-90")
      (fields (field (name "BOM_SUPPLIER PART") "C2345") (field (name "CONTRIBUTOR") "LCSC"))
      (libsource (lib "altium-import") (part "root_2_JTJ-USB-AF-08_"))
    )
  )
  (nets
    (net (code "1") (name "GND") (class "Default")
      (node (ref "C1") (pin "2") (pinfunction "2_2") (pintype "passive"))
      (node (ref "C2") (pin "1") (pinfunction "1_1") (pintype "passive"))
      (node (ref "C3") (pin "1") (pinfunction "1_1") (pintype "passive"))
      (node (ref "C4") (pin "2") (pinfunction "2_2") (pintype "passive"))
      (node (ref "J1") (pin "3") (pinfunction "3_3") (pintype "passive"))
      (node (ref "J1") (pin "4") (pinfunction "4_4") (pintype "passive"))
      (node (ref "J10") (pin "3") (pinfunction "3_3") (pintype "passive"))
      (node (ref "J9") (pin "10") (pinfunction "10_10") (pintype "passive"))
      (node (ref "J9") (pin "12") (pinfunction "12_12") (pintype "passive"))
      (node (ref "J9") (pin "2") (pinfunction "2_2") (pintype "passive"))
      (node (ref "J9") (pin "4") (pinfunction "4_4") (pintype "passive"))
      (node (ref "J9") (pin "6") (pinfunction "6_6") (pintype "passive"))
      (node (ref "J9") (pin "8") (pinfunction "8_8") (pintype "passive"))
      (node (ref "Q1") (pin "1") (pinfunction "e_1") (pintype "passive"))
      (node (ref "Q2") (pin "1") (pinfunction "e_1") (pintype "passive"))
      (node (ref "Q3") (pin "1") (pinfunction "e_1") (pintype "passive"))
      (node (ref "Q4") (pin "1") (pinfunction "e_1") (pintype "passive"))
      (node (ref "Q5") (pin "1") (pinfunction "e_1") (pintype "passive"))
      (node (ref "Q6") (pin "1") (pinfunction "e_1") (pintype "passive"))
      (node (ref "Q7") (pin "1") (pinfunction "e_1") (pintype "passive"))
      (node (ref "Q8") (pin "1") (pinfunction "e_1") (pintype "passive"))
      (node (ref "R62") (pin "1") (pinfunction "1_1") (pintype "passive"))
      (node (ref "R63") (pin "1") (pinfunction "1_1") (pintype "passive"))
      (node (ref "R64") (pin "1") (pinfunction "1_1") (pintype "passive"))
      (node (ref "R65") (pin "1") (pinfunction "1_1") (pintype "passive"))
      (node (ref "R66") (pin "1") (pinfunction "1_1") (pintype "passive"))
      (node (ref "R67") (pin "1") (pinfunction "1_1") (pintype "passive"))
      (node (ref "R68") (pin "1") (pinfunction "1_1") (pintype "passive"))
      (node (ref "R69") (pin "1") (pinfunction "1_1") (pintype "passive"))
      (node (ref "SEG1") (pin "3") (pinfunction "G1_3") (pintype "passive"))
      (node (ref "SEG1") (pin "5") (pinfunction "DP_5") (pintype "passive"))
      (node (ref "SEG1") (pin "8") (pinfunction "G2_8") (pintype "passive"))
      (node (ref "SEG2") (pin "3") (pinfunction "G1_3") (pintype "passive"))
      (node (ref "SEG2") (pin "5") (pinfunction "DP_5") (pintype "passive"))
      (node (ref "SEG2") (pin "8") (pinfunction "G2_8") (pintype "passive"))
      (node (ref "SEG3") (pin "3") (pinfunction "G1_3") (pintype "passive"))
      (node (ref "SEG3") (pin "5") (pinfunction "DP_5") (pintype "passive"))
      (node (ref "SEG3") (pin "8") (pinfunction "G2_8") (pintype "passive"))
      (node (ref "SEG4") (pin "3") (pinfunction "G1_3") (pintype "passive"))
      (node (ref "SEG4") (pin "5") (pinfunction "DP_5") (pintype "passive"))
      (node (ref "SEG4") (pin "8") (pinfunction "G2_8") (pintype "passive"))
      (node (ref "SEG5") (pin "3") (pinfunction "G1_3") (pintype "passive"))
      (node (ref "SEG5") (pin "5") (pinfunction "DP_5") (pintype "passive"))
      (node (ref "SEG5") (pin "8") (pinfunction "G2_8") (pintype "passive"))
      (node (ref "SEG6") (pin "3") (pinfunction "G1_3") (pintype "passive"))
      (node (ref "SEG6") (pin "5") (pinfunction "DP_5") (pintype "passive"))
      (node (ref "SEG6") (pin "8") (pinfunction "G2_8") (pintype "passive"))
      (node (ref "SW1") (pin "2") (pinfunction "2_2") (pintype "passive"))
      (node (ref "SW1") (pin "5") (pinfunction "5_5") (pintype "passive"))
      (node (ref "SW2") (pin "2") (pinfunction "2_2") (pintype "passive"))
      (node (ref "SW2") (pin "5") (pinfunction "5_5") (pintype "passive"))
      (node (ref "SW3") (pin "2") (pinfunction "2_2") (pintype "passive"))
      (node (ref "SW3") (pin "5") (pinfunction "5_5") (pintype "passive"))
      (node (ref "SW4") (pin "2") (pinfunction "2_2") (pintype "passive"))
      (node (ref "SW4") (pin "5") (pinfunction "5_5") (pintype "passive"))
      (node (ref "SW5") (pin "2") (pinfunction "2_2") (pintype "passive"))
      (node (ref "SW5") (pin "5") (pinfunction "5_5") (pintype "passive"))
      (node (ref "SW6") (pin "2") (pinfunction "2_2") (pintype "passive"))
      (node (ref "SW6") (pin "5") (pinfunction "5_5") (pintype "passive"))
      (node (ref "SW7") (pin "2") (pinfunction "2_2") (pintype "passive"))
      (node (ref "SW7") (pin "5") (pinfunction "5_5") (pintype "passive"))
      (node (ref "SW8") (pin "2") (pinfunction "2_2") (pintype "passive"))
      (node (ref "SW8") (pin "5") (pinfunction "5_5") (pintype "passive"))
      (node (ref "U1") (pin "1") (pinfunction "GND_1") (pintype "passive"))
      (node (ref "U12") (pin "5") (pinfunction "LESTROBE_5") (pintype "passive"))
      (node (ref "U12") (pin "8") (pinfunction "VSS_8") (pintype "passive"))
      (node (ref "U21") (pin "5") (pinfunction "LESTROBE_5") (pintype "passive"))
      (node (ref "U21") (pin "8") (pinfunction "VSS_8") (pintype "passive"))
      (node (ref "U26") (pin "5") (pinfunction "LESTROBE_5") (pintype "passive"))
      (node (ref "U26") (pin "8") (pinfunction "VSS_8") (pintype "passive"))
      (node (ref "U27") (pin "5") (pinfunction "LESTROBE_5") (pintype "passive"))
      (node (ref "U27") (pin "8") (pinfunction "VSS_8") (pintype "passive"))
      (node (ref "U3") (pin "1") (pinfunction "1_1") (pintype "passive"))
      (node (ref "U32") (pin "5") (pinfunction "LESTROBE_5") (pintype "passive"))
      (node (ref "U32") (pin "8") (pinfunction "VSS_8") (pintype "passive"))
      (node (ref "U41") (pin "5") (pinfunction "LESTROBE_5") (pintype "passive"))
      (node (ref "U41") (pin "8") (pinfunction "VSS_8") (pintype "passive"))
      (node (ref "U48") (pin "1") (pinfunction "1_1") (pintype "passive"))
      (node (ref "U49") (pin "1") (pinfunction "1_1") (pintype "passive"))
      (node (ref "U50") (pin "1") (pinfunction "1_1") (pintype "passive"))
      (node (ref "U51") (pin "1") (pinfunction "1_1") (pintype "passive"))
      (node (ref "U52") (pin "1") (pinfunction "1_1") (pintype "passive"))
      (node (ref "U53") (pin "1") (pinfunction "1_1") (pintype "passive"))
      (node (ref "USB1") (pin "4") (pinfunction "GND_4") (pintype "passive"))
      (node (ref "USB1") (pin "SH1") (pinfunction "SH1_SH1") (pintype "passive"))
      (node (ref "USB1") (pin "SH2") (pinfunction "SH2_SH2") (pintype "passive"))
    )
    (net (code "2") (name "Net-(D2-Pad1)") (class "Default")
      (node (ref "D2") (pin "1") (pinfunction "1_1") (pintype "passive"))
      (node (ref "R3") (pin "2") (pinfunction "2_2") (pintype "passive"))
    )
    (net (code "3") (name "Net-(J2-Pad1)") (class "Default")
      (node (ref "J2") (pin "1") (pinfunction "1_1") (pintype "passive"))
      (node (ref "SW1") (pin "4") (pinfunction "4_4") (pintype "passive"))
    )
    (net (code "4") (name "Net-(J2-Pad2)") (class "Default")
      (node (ref "J2") (pin "2") (pinfunction "2_2") (pintype "passive"))
      (node (ref "SW2") (pin "4") (pinfunction "4_4") (pintype "passive"))
    )
    (net (code "5") (name "Net-(J2-Pad3)") (class "Default")
      (node (ref "J2") (pin "3") (pinfunction "3_3") (pintype "passive"))
      (node (ref "SW3") (pin "4") (pinfunction "4_4") (pintype "passive"))
    )
    (net (code "6") (name "Net-(J2-Pad4)") (class "Default")
      (node (ref "J2") (pin "4") (pinfunction "4_4") (pintype "passive"))
      (node (ref "SW4") (pin "4") (pinfunction "4_4") (pintype "passive"))
    )
    (net (code "7") (name "Net-(J2-Pad5)") (class "Default")
      (node (ref "J2") (pin "5") (pinfunction "5_5") (pintype "passive"))
      (node (ref "SW8") (pin "4") (pinfunction "4_4") (pintype "passive"))
    )
    (net (code "8") (name "Net-(J2-Pad6)") (class "Default")
      (node (ref "J2") (pin "6") (pinfunction "6_6") (pintype "passive"))
      (node (ref "SW7") (pin "4") (pinfunction "4_4") (pintype "passive"))
    )
    (net (code "9") (name "Net-(J2-Pad7)") (class "Default")
      (node (ref "J2") (pin "7") (pinfunction "7_7") (pintype "passive"))
      (node (ref "SW6") (pin "4") (pinfunction "4_4") (pintype "passive"))
    )
    (net (code "10") (name "Net-(J2-Pad8)") (class "Default")
      (node (ref "J2") (pin "8") (pinfunction "8_8") (pintype "passive"))
      (node (ref "SW5") (pin "4") (pinfunction "4_4") (pintype "passive"))
    )
    (net (code "11") (name "Net-(J11-Pad1)") (class "Default")
      (node (ref "J11") (pin "1") (pinfunction "1_1") (pintype "passive"))
      (node (ref "R54") (pin "2") (pinfunction "2_2") (pintype "passive"))
      (node (ref "R69") (pin "2") (pinfunction "2_2") (pintype "passive"))
      (node (ref "U55") (pin "1") (pinfunction "1_1") (pintype "passive"))
    )
    (net (code "12") (name "Net-(J11-Pad2)") (class "Default")
      (node (ref "J11") (pin "2") (pinfunction "2_2") (pintype "passive"))
      (node (ref "R55") (pin "2") (pinfunction "2_2") (pintype "passive"))
      (node (ref "R68") (pin "2") (pinfunction "2_2") (pintype "passive"))
      (node (ref "U54") (pin "1") (pinfunction "1_1") (pintype "passive"))
    )
    (net (code "13") (name "Net-(J11-Pad3)") (class "Default")
      (node (ref "J11") (pin "3") (pinfunction "3_3") (pintype "passive"))
      (node (ref "R56") (pin "2") (pinfunction "2_2") (pintype "passive"))
      (node (ref "R67") (pin "2") (pinfunction "2_2") (pintype "passive"))
      (node (ref "U56") (pin "1") (pinfunction "1_1") (pintype "passive"))
    )
    (net (code "14") (name "Net-(J11-Pad4)") (class "Default")
      (node (ref "J11") (pin "4") (pinfunction "4_4") (pintype "passive"))
      (node (ref "R57") (pin "2") (pinfunction "2_2") (pintype "passive"))
      (node (ref "R66") (pin "2") (pinfunction "2_2") (pintype "passive"))
      (node (ref "U57") (pin "1") (pinfunction "1_1") (pintype "passive"))
    )
    (net (code "15") (name "Net-(J11-Pad5)") (class "Default")
      (node (ref "J11") (pin "5") (pinfunction "5_5") (pintype "passive"))
      (node (ref "R58") (pin "2") (pinfunction "2_2") (pintype "passive"))
      (node (ref "R65") (pin "2") (pinfunction "2_2") (pintype "passive"))
      (node (ref "U60") (pin "1") (pinfunction "1_1") (pintype "passive"))
    )
    (net (code "16") (name "Net-(J11-Pad6)") (class "Default")
      (node (ref "J11") (pin "6") (pinfunction "6_6") (pintype "passive"))
      (node (ref "R59") (pin "2") (pinfunction "2_2") (pintype "passive"))
      (node (ref "R64") (pin "2") (pinfunction "2_2") (pintype "passive"))
      (node (ref "U61") (pin "1") (pinfunction "1_1") (pintype "passive"))
    )
    (net (code "17") (name "Net-(J11-Pad7)") (class "Default")
      (node (ref "J11") (pin "7") (pinfunction "7_7") (pintype "passive"))
      (node (ref "R60") (pin "2") (pinfunction "2_2") (pintype "passive"))
      (node (ref "R63") (pin "2") (pinfunction "2_2") (pintype "passive"))
      (node (ref "U59") (pin "1") (pinfunction "1_1") (pintype "passive"))
    )
    (net (code "18") (name "Net-(J11-Pad8)") (class "Default")
      (node (ref "J11") (pin "8") (pinfunction "8_8") (pintype "passive"))
      (node (ref "R61") (pin "2") (pinfunction "2_2") (pintype "passive"))
      (node (ref "R62") (pin "2") (pinfunction "2_2") (pintype "passive"))
      (node (ref "U58") (pin "1") (pinfunction "1_1") (pintype "passive"))
    )
    (net (code "19") (name "Net-(LED1-Pad1)") (class "Default")
      (node (ref "LED1") (pin "1") (pinfunction "1_1") (pintype "passive"))
      (node (ref "R46") (pin "1") (pinfunction "1_1") (pintype "passive"))
    )
    (net (code "20") (name "Net-(LED2-Pad1)") (class "Default")
      (node (ref "LED2") (pin "1") (pinfunction "1_1") (pintype "passive"))
      (node (ref "R47") (pin "1") (pinfunction "1_1") (pintype "passive"))
    )
    (net (code "21") (name "Net-(LED3-Pad1)") (class "Default")
      (node (ref "LED3") (pin "1") (pinfunction "1_1") (pintype "passive"))
      (node (ref "R48") (pin "1") (pinfunction "1_1") (pintype "passive"))
    )
    (net (code "22") (name "Net-(LED4-Pad1)") (class "Default")
      (node (ref "LED4") (pin "1") (pinfunction "1_1") (pintype "passive"))
      (node (ref "R49") (pin "1") (pinfunction "1_1") (pintype "passive"))
    )
    (net (code "23") (name "Net-(LED5-Pad1)") (class "Default")
      (node (ref "LED5") (pin "1") (pinfunction "1_1") (pintype "passive"))
      (node (ref "R50") (pin "1") (pinfunction "1_1") (pintype "passive"))
    )
    (net (code "24") (name "Net-(LED6-Pad1)") (class "Default")
      (node (ref "LED6") (pin "1") (pinfunction "1_1") (pintype "passive"))
      (node (ref "R51") (pin "1") (pinfunction "1_1") (pintype "passive"))
    )
    (net (code "25") (name "Net-(LED7-Pad1)") (class "Default")
      (node (ref "LED7") (pin "1") (pinfunction "1_1") (pintype "passive"))
      (node (ref "R52") (pin "1") (pinfunction "1_1") (pintype "passive"))
    )
    (net (code "26") (name "Net-(LED8-Pad1)") (class "Default")
      (node (ref "LED8") (pin "1") (pinfunction "1_1") (pintype "passive"))
      (node (ref "R53") (pin "1") (pinfunction "1_1") (pintype "passive"))
    )
    (net (code "27") (name "Net-(Q1-b)") (class "Default")
      (node (ref "Q1") (pin "2") (pinfunction "b_2") (pintype "passive"))
      (node (ref "R55") (pin "1") (pinfunction "1_1") (pintype "passive"))
    )
    (net (code "28") (name "Net-(Q1-c)") (class "Default")
      (node (ref "LED1") (pin "2") (pinfunction "2_2") (pintype "passive"))
      (node (ref "Q1") (pin "3") (pinfunction "c_3") (pintype "passive"))
    )
    (net (code "29") (name "Net-(Q2-b)") (class "Default")
      (node (ref "Q2") (pin "2") (pinfunction "b_2") (pintype "passive"))
      (node (ref "R54") (pin "1") (pinfunction "1_1") (pintype "passive"))
    )
    (net (code "30") (name "Net-(Q2-c)") (class "Default")
      (node (ref "LED2") (pin "2") (pinfunction "2_2") (pintype "passive"))
      (node (ref "Q2") (pin "3") (pinfunction "c_3") (pintype "passive"))
    )
    (net (code "31") (name "Net-(Q3-b)") (class "Default")
      (node (ref "Q3") (pin "2") (pinfunction "b_2") (pintype "passive"))
      (node (ref "R56") (pin "1") (pinfunction "1_1") (pintype "passive"))
    )
    (net (code "32") (name "Net-(Q3-c)") (class "Default")
      (node (ref "LED3") (pin "2") (pinfunction "2_2") (pintype "passive"))
      (node (ref "Q3") (pin "3") (pinfunction "c_3") (pintype "passive"))
    )
    (net (code "33") (name "Net-(Q4-b)") (class "Default")
      (node (ref "Q4") (pin "2") (pinfunction "b_2") (pintype "passive"))
      (node (ref "R57") (pin "1") (pinfunction "1_1") (pintype "passive"))
    )
    (net (code "34") (name "Net-(Q4-c)") (class "Default")
      (node (ref "LED4") (pin "2") (pinfunction "2_2") (pintype "passive"))
      (node (ref "Q4") (pin "3") (pinfunction "c_3") (pintype "passive"))
    )
    (net (code "35") (name "Net-(Q5-b)") (class "Default")
      (node (ref "Q5") (pin "2") (pinfunction "b_2") (pintype "passive"))
      (node (ref "R61") (pin "1") (pinfunction "1_1") (pintype "passive"))
    )
    (net (code "36") (name "Net-(Q5-c)") (class "Default")
      (node (ref "LED5") (pin "2") (pinfunction "2_2") (pintype "passive"))
      (node (ref "Q5") (pin "3") (pinfunction "c_3") (pintype "passive"))
    )
    (net (code "37") (name "Net-(Q6-b)") (class "Default")
      (node (ref "Q6") (pin "2") (pinfunction "b_2") (pintype "passive"))
      (node (ref "R60") (pin "1") (pinfunction "1_1") (pintype "passive"))
    )
    (net (code "38") (name "Net-(Q6-c)") (class "Default")
      (node (ref "LED6") (pin "2") (pinfunction "2_2") (pintype "passive"))
      (node (ref "Q6") (pin "3") (pinfunction "c_3") (pintype "passive"))
    )
    (net (code "39") (name "Net-(Q7-b)") (class "Default")
      (node (ref "Q7") (pin "2") (pinfunction "b_2") (pintype "passive"))
      (node (ref "R58") (pin "1") (pinfunction "1_1") (pintype "passive"))
    )
    (net (code "40") (name "Net-(Q7-c)") (class "Default")
      (node (ref "LED7") (pin "2") (pinfunction "2_2") (pintype "passive"))
      (node (ref "Q7") (pin "3") (pinfunction "c_3") (pintype "passive"))
    )
    (net (code "41") (name "Net-(Q8-b)") (class "Default")
      (node (ref "Q8") (pin "2") (pinfunction "b_2") (pintype "passive"))
      (node (ref "R59") (pin "1") (pinfunction "1_1") (pintype "passive"))
    )
    (net (code "42") (name "Net-(Q8-c)") (class "Default")
      (node (ref "LED8") (pin "2") (pinfunction "2_2") (pintype "passive"))
      (node (ref "Q8") (pin "3") (pinfunction "c_3") (pintype "passive"))
    )
    (net (code "43") (name "Net-(R1-Pad1)") (class "Default")
      (node (ref "R1") (pin "1") (pinfunction "1_1") (pintype "passive"))
      (node (ref "R2") (pin "1") (pinfunction "1_1") (pintype "passive"))
    )
    (net (code "44") (name "Net-(R1-Pad4)") (class "Default")
      (node (ref "R1") (pin "4") (pinfunction "4_4") (pintype "passive"))
      (node (ref "R1") (pin "5") (pinfunction "5_5") (pintype "passive"))
      (node (ref "R3") (pin "1") (pinfunction "1_1") (pintype "passive"))
    )
    (net (code "45") (name "Net-(SEG1-A)") (class "Default")
      (node (ref "R4") (pin "2") (pinfunction "2_2") (pintype "passive"))
      (node (ref "SEG1") (pin "7") (pinfunction "A_7") (pintype "passive"))
    )
    (net (code "46") (name "Net-(SEG1-B)") (class "Default")
      (node (ref "R5") (pin "2") (pinfunction "2_2") (pintype "passive"))
      (node (ref "SEG1") (pin "6") (pinfunction "B_6") (pintype "passive"))
    )
    (net (code "47") (name "Net-(SEG1-C)") (class "Default")
      (node (ref "R6") (pin "2") (pinfunction "2_2") (pintype "passive"))
      (node (ref "SEG1") (pin "4") (pinfunction "C_4") (pintype "passive"))
    )
    (net (code "48") (name "Net-(SEG1-D)") (class "Default")
      (node (ref "R7") (pin "2") (pinfunction "2_2") (pintype "passive"))
      (node (ref "SEG1") (pin "2") (pinfunction "D_2") (pintype "passive"))
    )
    (net (code "49") (name "Net-(SEG1-E)") (class "Default")
      (node (ref "R8") (pin "2") (pinfunction "2_2") (pintype "passive"))
      (node (ref "SEG1") (pin "1") (pinfunction "E_1") (pintype "passive"))
    )
    (net (code "50") (name "Net-(SEG1-F)") (class "Default")
      (node (ref "R9") (pin "2") (pinfunction "2_2") (pintype "passive"))
      (node (ref "SEG1") (pin "9") (pinfunction "F_9") (pintype "passive"))
    )
    (net (code "51") (name "Net-(SEG1-G)") (class "Default")
      (node (ref "R10") (pin "2") (pinfunction "2_2") (pintype "passive"))
      (node (ref "SEG1") (pin "10") (pinfunction "G_10") (pintype "passive"))
    )
    (net (code "52") (name "Net-(SEG2-A)") (class "Default")
      (node (ref "R17") (pin "2") (pinfunction "2_2") (pintype "passive"))
      (node (ref "SEG2") (pin "7") (pinfunction "A_7") (pintype "passive"))
    )
    (net (code "53") (name "Net-(SEG2-B)") (class "Default")
      (node (ref "R16") (pin "2") (pinfunction "2_2") (pintype "passive"))
      (node (ref "SEG2") (pin "6") (pinfunction "B_6") (pintype "passive"))
    )
    (net (code "54") (name "Net-(SEG2-C)") (class "Default")
      (node (ref "R15") (pin "2") (pinfunction "2_2") (pintype "passive"))
      (node (ref "SEG2") (pin "4") (pinfunction "C_4") (pintype "passive"))
    )
    (net (code "55") (name "Net-(SEG2-D)") (class "Default")
      (node (ref "R14") (pin "2") (pinfunction "2_2") (pintype "passive"))
      (node (ref "SEG2") (pin "2") (pinfunction "D_2") (pintype "passive"))
    )
    (net (code "56") (name "Net-(SEG2-E)") (class "Default")
      (node (ref "R13") (pin "2") (pinfunction "2_2") (pintype "passive"))
      (node (ref "SEG2") (pin "1") (pinfunction "E_1") (pintype "passive"))
    )
    (net (code "57") (name "Net-(SEG2-F)") (class "Default")
      (node (ref "R12") (pin "2") (pinfunction "2_2") (pintype "passive"))
      (node (ref "SEG2") (pin "9") (pinfunction "F_9") (pintype "passive"))
    )
    (net (code "58") (name "Net-(SEG2-G)") (class "Default")
      (node (ref "R11") (pin "2") (pinfunction "2_2") (pintype "passive"))
      (node (ref "SEG2") (pin "10") (pinfunction "G_10") (pintype "passive"))
    )
    (net (code "59") (name "Net-(SEG3-A)") (class "Default")
      (node (ref "R24") (pin "2") (pinfunction "2_2") (pintype "passive"))
      (node (ref "SEG3") (pin "7") (pinfunction "A_7") (pintype "passive"))
    )
    (net (code "60") (name "Net-(SEG3-B)") (class "Default")
      (node (ref "R23") (pin "2") (pinfunction "2_2") (pintype "passive"))
      (node (ref "SEG3") (pin "6") (pinfunction "B_6") (pintype "passive"))
    )
    (net (code "61") (name "Net-(SEG3-C)") (class "Default")
      (node (ref "R22") (pin "2") (pinfunction "2_2") (pintype "passive"))
      (node (ref "SEG3") (pin "4") (pinfunction "C_4") (pintype "passive"))
    )
    (net (code "62") (name "Net-(SEG3-D)") (class "Default")
      (node (ref "R21") (pin "2") (pinfunction "2_2") (pintype "passive"))
      (node (ref "SEG3") (pin "2") (pinfunction "D_2") (pintype "passive"))
    )
    (net (code "63") (name "Net-(SEG3-E)") (class "Default")
      (node (ref "R20") (pin "2") (pinfunction "2_2") (pintype "passive"))
      (node (ref "SEG3") (pin "1") (pinfunction "E_1") (pintype "passive"))
    )
    (net (code "64") (name "Net-(SEG3-F)") (class "Default")
      (node (ref "R19") (pin "2") (pinfunction "2_2") (pintype "passive"))
      (node (ref "SEG3") (pin "9") (pinfunction "F_9") (pintype "passive"))
    )
    (net (code "65") (name "Net-(SEG3-G)") (class "Default")
      (node (ref "R18") (pin "2") (pinfunction "2_2") (pintype "passive"))
      (node (ref "SEG3") (pin "10") (pinfunction "G_10") (pintype "passive"))
    )
    (net (code "66") (name "Net-(SEG4-A)") (class "Default")
      (node (ref "R25") (pin "2") (pinfunction "2_2") (pintype "passive"))
      (node (ref "SEG4") (pin "7") (pinfunction "A_7") (pintype "passive"))
    )
    (net (code "67") (name "Net-(SEG4-B)") (class "Default")
      (node (ref "R26") (pin "2") (pinfunction "2_2") (pintype "passive"))
      (node (ref "SEG4") (pin "6") (pinfunction "B_6") (pintype "passive"))
    )
    (net (code "68") (name "Net-(SEG4-C)") (class "Default")
      (node (ref "R27") (pin "2") (pinfunction "2_2") (pintype "passive"))
      (node (ref "SEG4") (pin "4") (pinfunction "C_4") (pintype "passive"))
    )
    (net (code "69") (name "Net-(SEG4-D)") (class "Default")
      (node (ref "R28") (pin "2") (pinfunction "2_2") (pintype "passive"))
      (node (ref "SEG4") (pin "2") (pinfunction "D_2") (pintype "passive"))
    )
    (net (code "70") (name "Net-(SEG4-E)") (class "Default")
      (node (ref "R29") (pin "2") (pinfunction "2_2") (pintype "passive"))
      (node (ref "SEG4") (pin "1") (pinfunction "E_1") (pintype "passive"))
    )
    (net (code "71") (name "Net-(SEG4-F)") (class "Default")
      (node (ref "R30") (pin "2") (pinfunction "2_2") (pintype "passive"))
      (node (ref "SEG4") (pin "9") (pinfunction "F_9") (pintype "passive"))
    )
    (net (code "72") (name "Net-(SEG4-G)") (class "Default")
      (node (ref "R31") (pin "2") (pinfunction "2_2") (pintype "passive"))
      (node (ref "SEG4") (pin "10") (pinfunction "G_10") (pintype "passive"))
    )
    (net (code "73") (name "Net-(SEG5-A)") (class "Default")
      (node (ref "R32") (pin "2") (pinfunction "2_2") (pintype "passive"))
      (node (ref "SEG5") (pin "7") (pinfunction "A_7") (pintype "passive"))
    )
    (net (code "74") (name "Net-(SEG5-B)") (class "Default")
      (node (ref "R33") (pin "2") (pinfunction "2_2") (pintype "passive"))
      (node (ref "SEG5") (pin "6") (pinfunction "B_6") (pintype "passive"))
    )
    (net (code "75") (name "Net-(SEG5-C)") (class "Default")
      (node (ref "R34") (pin "2") (pinfunction "2_2") (pintype "passive"))
      (node (ref "SEG5") (pin "4") (pinfunction "C_4") (pintype "passive"))
    )
    (net (code "76") (name "Net-(SEG5-D)") (class "Default")
      (node (ref "R35") (pin "2") (pinfunction "2_2") (pintype "passive"))
      (node (ref "SEG5") (pin "2") (pinfunction "D_2") (pintype "passive"))
    )
    (net (code "77") (name "Net-(SEG5-E)") (class "Default")
      (node (ref "R36") (pin "2") (pinfunction "2_2") (pintype "passive"))
      (node (ref "SEG5") (pin "1") (pinfunction "E_1") (pintype "passive"))
    )
    (net (code "78") (name "Net-(SEG5-F)") (class "Default")
      (node (ref "R37") (pin "2") (pinfunction "2_2") (pintype "passive"))
      (node (ref "SEG5") (pin "9") (pinfunction "F_9") (pintype "passive"))
    )
    (net (code "79") (name "Net-(SEG5-G)") (class "Default")
      (node (ref "R38") (pin "2") (pinfunction "2_2") (pintype "passive"))
      (node (ref "SEG5") (pin "10") (pinfunction "G_10") (pintype "passive"))
    )
    (net (code "80") (name "Net-(SEG6-A)") (class "Default")
      (node (ref "R45") (pin "2") (pinfunction "2_2") (pintype "passive"))
      (node (ref "SEG6") (pin "7") (pinfunction "A_7") (pintype "passive"))
    )
    (net (code "81") (name "Net-(SEG6-B)") (class "Default")
      (node (ref "R44") (pin "2") (pinfunction "2_2") (pintype "passive"))
      (node (ref "SEG6") (pin "6") (pinfunction "B_6") (pintype "passive"))
    )
    (net (code "82") (name "Net-(SEG6-C)") (class "Default")
      (node (ref "R43") (pin "2") (pinfunction "2_2") (pintype "passive"))
      (node (ref "SEG6") (pin "4") (pinfunction "C_4") (pintype "passive"))
    )
    (net (code "83") (name "Net-(SEG6-D)") (class "Default")
      (node (ref "R42") (pin "2") (pinfunction "2_2") (pintype "passive"))
      (node (ref "SEG6") (pin "2") (pinfunction "D_2") (pintype "passive"))
    )
    (net (code "84") (name "Net-(SEG6-E)") (class "Default")
      (node (ref "R41") (pin "2") (pinfunction "2_2") (pintype "passive"))
      (node (ref "SEG6") (pin "1") (pinfunction "E_1") (pintype "passive"))
    )
    (net (code "85") (name "Net-(SEG6-F)") (class "Default")
      (node (ref "R40") (pin "2") (pinfunction "2_2") (pintype "passive"))
      (node (ref "SEG6") (pin "9") (pinfunction "F_9") (pintype "passive"))
    )
    (net (code "86") (name "Net-(SEG6-G)") (class "Default")
      (node (ref "R39") (pin "2") (pinfunction "2_2") (pintype "passive"))
      (node (ref "SEG6") (pin "10") (pinfunction "G_10") (pintype "passive"))
    )
    (net (code "87") (name "Net-(SW1-Pad3)") (class "Default")
      (node (ref "SW1") (pin "3") (pinfunction "3_3") (pintype "passive"))
      (node (ref "U5") (pin "1") (pinfunction "1_1") (pintype "passive"))
    )
    (net (code "88") (name "Net-(SW2-Pad3)") (class "Default")
      (node (ref "SW2") (pin "3") (pinfunction "3_3") (pintype "passive"))
      (node (ref "U4") (pin "1") (pinfunction "1_1") (pintype "passive"))
    )
    (net (code "89") (name "Net-(SW3-Pad3)") (class "Default")
      (node (ref "SW3") (pin "3") (pinfunction "3_3") (pintype "passive"))
      (node (ref "U6") (pin "1") (pinfunction "1_1") (pintype "passive"))
    )
    (net (code "90") (name "Net-(SW4-Pad3)") (class "Default")
      (node (ref "SW4") (pin "3") (pinfunction "3_3") (pintype "passive"))
      (node (ref "U7") (pin "1") (pinfunction "1_1") (pintype "passive"))
    )
    (net (code "91") (name "Net-(SW5-Pad3)") (class "Default")
      (node (ref "SW5") (pin "3") (pinfunction "3_3") (pintype "passive"))
      (node (ref "U8") (pin "1") (pinfunction "1_1") (pintype "passive"))
    )
    (net (code "92") (name "Net-(SW6-Pad3)") (class "Default")
      (node (ref "SW6") (pin "3") (pinfunction "3_3") (pintype "passive"))
      (node (ref "U9") (pin "1") (pinfunction "1_1") (pintype "passive"))
    )
    (net (code "93") (name "Net-(SW7-Pad3)") (class "Default")
      (node (ref "SW7") (pin "3") (pinfunction "3_3") (pintype "passive"))
      (node (ref "U10") (pin "1") (pinfunction "1_1") (pintype "passive"))
    )
    (net (code "94") (name "Net-(SW8-Pad3)") (class "Default")
      (node (ref "SW8") (pin "3") (pinfunction "3_3") (pintype "passive"))
      (node (ref "U11") (pin "1") (pinfunction "1_1") (pintype "passive"))
    )
    (net (code "95") (name "Net-(U1-Controlvoltage)") (class "Default")
      (node (ref "C2") (pin "2") (pinfunction "2_2") (pintype "passive"))
      (node (ref "U1") (pin "5") (pinfunction "Controlvoltage_5") (pintype "passive"))
    )
    (net (code "96") (name "Net-(U1-Discharge)") (class "Default")
      (node (ref "D1") (pin "2") (pinfunction "2_2") (pintype "passive"))
      (node (ref "R1") (pin "2") (pinfunction "2_2") (pintype "passive"))
      (node (ref "R1") (pin "3") (pinfunction "3_3") (pintype "passive"))
      (node (ref "R1") (pin "6") (pinfunction "6_6") (pintype "passive"))
      (node (ref "U1") (pin "7") (pinfunction "Discharge_7") (pintype "passive"))
    )
    (net (code "97") (name "Net-(U1-Output)") (class "Default")
      (node (ref "J1") (pin "1") (pinfunction "1_1") (pintype "passive"))
      (node (ref "J1") (pin "2") (pinfunction "2_2") (pintype "passive"))
      (node (ref "J10") (pin "2") (pinfunction "2_2") (pintype "passive"))
      (node (ref "U1") (pin "3") (pinfunction "Output_3") (pintype "passive"))
      (node (ref "U2") (pin "1") (pinfunction "1_1") (pintype "passive"))
    )
    (net (code "98") (name "Net-(U1-Threshold)") (class "Default")
      (node (ref "C1") (pin "1") (pinfunction "1_1") (pintype "passive"))
      (node (ref "D1") (pin "1") (pinfunction "1_1") (pintype "passive"))
      (node (ref "D2") (pin "2") (pinfunction "2_2") (pintype "passive"))
      (node (ref "U1") (pin "2") (pinfunction "Trigger_2") (pintype "passive"))
      (node (ref "U1") (pin "6") (pinfunction "Threshold_6") (pintype "passive"))
    )
    (net (code "99") (name "Net-(U12-A)") (class "Default")
      (node (ref "R4") (pin "1") (pinfunction "1_1") (pintype "passive"))
      (node (ref "U12") (pin "13") (pinfunction "A_13") (pintype "passive"))
    )
    (net (code "100") (name "Net-(U12-A{slash}2)") (class "Default")
      (node (ref "J3") (pin "1") (pinfunction "1_1") (pintype "passive"))
      (node (ref "U12") (pin "7") (pinfunction "A/2_7") (pintype "passive"))
      (node (ref "U13") (pin "1") (pinfunction "1_1") (pintype "passive"))
    )
    (net (code "101") (name "Net-(U12-B)") (class "Default")
      (node (ref "R5") (pin "1") (pinfunction "1_1") (pintype "passive"))
      (node (ref "U12") (pin "12") (pinfunction "B_12") (pintype "passive"))
    )
    (net (code "102") (name "Net-(U12-B{slash}2)") (class "Default")
      (node (ref "J3") (pin "2") (pinfunction "2_2") (pintype "passive"))
      (node (ref "U12") (pin "1") (pinfunction "B/2_1") (pintype "passive"))
      (node (ref "U14") (pin "1") (pinfunction "1_1") (pintype "passive"))
    )
    (net (code "103") (name "Net-(U12-C)") (class "Default")
      (node (ref "R6") (pin "1") (pinfunction "1_1") (pintype "passive"))
      (node (ref "U12") (pin "11") (pinfunction "C_11") (pintype "passive"))
    )
    (net (code "104") (name "Net-(U12-C{slash}2)") (class "Default")
      (node (ref "J3") (pin "3") (pinfunction "3_3") (pintype "passive"))
      (node (ref "U12") (pin "2") (pinfunction "C/2_2") (pintype "passive"))
      (node (ref "U15") (pin "1") (pinfunction "1_1") (pintype "passive"))
    )
    (net (code "105") (name "Net-(U12-D)") (class "Default")
      (node (ref "R7") (pin "1") (pinfunction "1_1") (pintype "passive"))
      (node (ref "U12") (pin "10") (pinfunction "D_10") (pintype "passive"))
    )
    (net (code "106") (name "Net-(U12-D{slash}2)") (class "Default")
      (node (ref "J3") (pin "4") (pinfunction "4_4") (pintype "passive"))
      (node (ref "U12") (pin "6") (pinfunction "D/2_6") (pintype "passive"))
      (node (ref "U16") (pin "1") (pinfunction "1_1") (pintype "passive"))
    )
    (net (code "107") (name "Net-(U12-E)") (class "Default")
      (node (ref "R8") (pin "1") (pinfunction "1_1") (pintype "passive"))
      (node (ref "U12") (pin "9") (pinfunction "E_9") (pintype "passive"))
    )
    (net (code "108") (name "Net-(U12-F)") (class "Default")
      (node (ref "R9") (pin "1") (pinfunction "1_1") (pintype "passive"))
      (node (ref "U12") (pin "15") (pinfunction "F_15") (pintype "passive"))
    )
    (net (code "109") (name "Net-(U12-G)") (class "Default")
      (node (ref "R10") (pin "1") (pinfunction "1_1") (pintype "passive"))
      (node (ref "U12") (pin "14") (pinfunction "G_14") (pintype "passive"))
    )
    (net (code "110") (name "Net-(U21-A)") (class "Default")
      (node (ref "R17") (pin "1") (pinfunction "1_1") (pintype "passive"))
      (node (ref "U21") (pin "13") (pinfunction "A_13") (pintype "passive"))
    )
    (net (code "111") (name "Net-(U21-A{slash}2)") (class "Default")
      (node (ref "J4") (pin "1") (pinfunction "1_1") (pintype "passive"))
      (node (ref "U20") (pin "1") (pinfunction "1_1") (pintype "passive"))
      (node (ref "U21") (pin "7") (pinfunction "A/2_7") (pintype "passive"))
    )
    (net (code "112") (name "Net-(U21-B)") (class "Default")
      (node (ref "R16") (pin "1") (pinfunction "1_1") (pintype "passive"))
      (node (ref "U21") (pin "12") (pinfunction "B_12") (pintype "passive"))
    )
    (net (code "113") (name "Net-(U21-B{slash}2)") (class "Default")
      (node (ref "J4") (pin "2") (pinfunction "2_2") (pintype "passive"))
      (node (ref "U19") (pin "1") (pinfunction "1_1") (pintype "passive"))
      (node (ref "U21") (pin "1") (pinfunction "B/2_1") (pintype "passive"))
    )
    (net (code "114") (name "Net-(U21-C)") (class "Default")
      (node (ref "R15") (pin "1") (pinfunction "1_1") (pintype "passive"))
      (node (ref "U21") (pin "11") (pinfunction "C_11") (pintype "passive"))
    )
    (net (code "115") (name "Net-(U21-C{slash}2)") (class "Default")
      (node (ref "J4") (pin "3") (pinfunction "3_3") (pintype "passive"))
      (node (ref "U18") (pin "1") (pinfunction "1_1") (pintype "passive"))
      (node (ref "U21") (pin "2") (pinfunction "C/2_2") (pintype "passive"))
    )
    (net (code "116") (name "Net-(U21-D)") (class "Default")
      (node (ref "R14") (pin "1") (pinfunction "1_1") (pintype "passive"))
      (node (ref "U21") (pin "10") (pinfunction "D_10") (pintype "passive"))
    )
    (net (code "117") (name "Net-(U21-D{slash}2)") (class "Default")
      (node (ref "J4") (pin "4") (pinfunction "4_4") (pintype "passive"))
      (node (ref "U17") (pin "1") (pinfunction "1_1") (pintype "passive"))
      (node (ref "U21") (pin "6") (pinfunction "D/2_6") (pintype "passive"))
    )
    (net (code "118") (name "Net-(U21-E)") (class "Default")
      (node (ref "R13") (pin "1") (pinfunction "1_1") (pintype "passive"))
      (node (ref "U21") (pin "9") (pinfunction "E_9") (pintype "passive"))
    )
    (net (code "119") (name "Net-(U21-F)") (class "Default")
      (node (ref "R12") (pin "1") (pinfunction "1_1") (pintype "passive"))
      (node (ref "U21") (pin "15") (pinfunction "F_15") (pintype "passive"))
    )
    (net (code "120") (name "Net-(U21-G)") (class "Default")
      (node (ref "R11") (pin "1") (pinfunction "1_1") (pintype "passive"))
      (node (ref "U21") (pin "14") (pinfunction "G_14") (pintype "passive"))
    )
    (net (code "121") (name "Net-(U26-A)") (class "Default")
      (node (ref "R24") (pin "1") (pinfunction "1_1") (pintype "passive"))
      (node (ref "U26") (pin "13") (pinfunction "A_13") (pintype "passive"))
    )
    (net (code "122") (name "Net-(U26-A{slash}2)") (class "Default")
      (node (ref "J5") (pin "1") (pinfunction "1_1") (pintype "passive"))
      (node (ref "U25") (pin "1") (pinfunction "1_1") (pintype "passive"))
      (node (ref "U26") (pin "7") (pinfunction "A/2_7") (pintype "passive"))
    )
    (net (code "123") (name "Net-(U26-B)") (class "Default")
      (node (ref "R23") (pin "1") (pinfunction "1_1") (pintype "passive"))
      (node (ref "U26") (pin "12") (pinfunction "B_12") (pintype "passive"))
    )
    (net (code "124") (name "Net-(U26-B{slash}2)") (class "Default")
      (node (ref "J5") (pin "2") (pinfunction "2_2") (pintype "passive"))
      (node (ref "U24") (pin "1") (pinfunction "1_1") (pintype "passive"))
      (node (ref "U26") (pin "1") (pinfunction "B/2_1") (pintype "passive"))
    )
    (net (code "125") (name "Net-(U26-C)") (class "Default")
      (node (ref "R22") (pin "1") (pinfunction "1_1") (pintype "passive"))
      (node (ref "U26") (pin "11") (pinfunction "C_11") (pintype "passive"))
    )
    (net (code "126") (name "Net-(U26-C{slash}2)") (class "Default")
      (node (ref "J5") (pin "3") (pinfunction "3_3") (pintype "passive"))
      (node (ref "U23") (pin "1") (pinfunction "1_1") (pintype "passive"))
      (node (ref "U26") (pin "2") (pinfunction "C/2_2") (pintype "passive"))
    )
    (net (code "127") (name "Net-(U26-D)") (class "Default")
      (node (ref "R21") (pin "1") (pinfunction "1_1") (pintype "passive"))
      (node (ref "U26") (pin "10") (pinfunction "D_10") (pintype "passive"))
    )
    (net (code "128") (name "Net-(U26-D{slash}2)") (class "Default")
      (node (ref "J5") (pin "4") (pinfunction "4_4") (pintype "passive"))
      (node (ref "U22") (pin "1") (pinfunction "1_1") (pintype "passive"))
      (node (ref "U26") (pin "6") (pinfunction "D/2_6") (pintype "passive"))
    )
    (net (code "129") (name "Net-(U26-E)") (class "Default")
      (node (ref "R20") (pin "1") (pinfunction "1_1") (pintype "passive"))
      (node (ref "U26") (pin "9") (pinfunction "E_9") (pintype "passive"))
    )
    (net (code "130") (name "Net-(U26-F)") (class "Default")
      (node (ref "R19") (pin "1") (pinfunction "1_1") (pintype "passive"))
      (node (ref "U26") (pin "15") (pinfunction "F_15") (pintype "passive"))
    )
    (net (code "131") (name "Net-(U26-G)") (class "Default")
      (node (ref "R18") (pin "1") (pinfunction "1_1") (pintype "passive"))
      (node (ref "U26") (pin "14") (pinfunction "G_14") (pintype "passive"))
    )
    (net (code "132") (name "Net-(U27-A)") (class "Default")
      (node (ref "R25") (pin "1") (pinfunction "1_1") (pintype "passive"))
      (node (ref "U27") (pin "13") (pinfunction "A_13") (pintype "passive"))
    )
    (net (code "133") (name "Net-(U27-A{slash}2)") (class "Default")
      (node (ref "J6") (pin "1") (pinfunction "1_1") (pintype "passive"))
      (node (ref "U27") (pin "7") (pinfunction "A/2_7") (pintype "passive"))
      (node (ref "U28") (pin "1") (pinfunction "1_1") (pintype "passive"))
    )
    (net (code "134") (name "Net-(U27-B)") (class "Default")
      (node (ref "R26") (pin "1") (pinfunction "1_1") (pintype "passive"))
      (node (ref "U27") (pin "12") (pinfunction "B_12") (pintype "passive"))
    )
    (net (code "135") (name "Net-(U27-B{slash}2)") (class "Default")
      (node (ref "J6") (pin "2") (pinfunction "2_2") (pintype "passive"))
      (node (ref "U27") (pin "1") (pinfunction "B/2_1") (pintype "passive"))
      (node (ref "U29") (pin "1") (pinfunction "1_1") (pintype "passive"))
    )
    (net (code "136") (name "Net-(U27-C)") (class "Default")
      (node (ref "R27") (pin "1") (pinfunction "1_1") (pintype "passive"))
      (node (ref "U27") (pin "11") (pinfunction "C_11") (pintype "passive"))
    )
    (net (code "137") (name "Net-(U27-C{slash}2)") (class "Default")
      (node (ref "J6") (pin "3") (pinfunction "3_3") (pintype "passive"))
      (node (ref "U27") (pin "2") (pinfunction "C/2_2") (pintype "passive"))
      (node (ref "U30") (pin "1") (pinfunction "1_1") (pintype "passive"))
    )
    (net (code "138") (name "Net-(U27-D)") (class "Default")
      (node (ref "R28") (pin "1") (pinfunction "1_1") (pintype "passive"))
      (node (ref "U27") (pin "10") (pinfunction "D_10") (pintype "passive"))
    )
    (net (code "139") (name "Net-(U27-D{slash}2)") (class "Default")
      (node (ref "J6") (pin "4") (pinfunction "4_4") (pintype "passive"))
      (node (ref "U27") (pin "6") (pinfunction "D/2_6") (pintype "passive"))
      (node (ref "U31") (pin "1") (pinfunction "1_1") (pintype "passive"))
    )
    (net (code "140") (name "Net-(U27-E)") (class "Default")
      (node (ref "R29") (pin "1") (pinfunction "1_1") (pintype "passive"))
      (node (ref "U27") (pin "9") (pinfunction "E_9") (pintype "passive"))
    )
    (net (code "141") (name "Net-(U27-F)") (class "Default")
      (node (ref "R30") (pin "1") (pinfunction "1_1") (pintype "passive"))
      (node (ref "U27") (pin "15") (pinfunction "F_15") (pintype "passive"))
    )
    (net (code "142") (name "Net-(U27-G)") (class "Default")
      (node (ref "R31") (pin "1") (pinfunction "1_1") (pintype "passive"))
      (node (ref "U27") (pin "14") (pinfunction "G_14") (pintype "passive"))
    )
    (net (code "143") (name "Net-(U32-A)") (class "Default")
      (node (ref "R32") (pin "1") (pinfunction "1_1") (pintype "passive"))
      (node (ref "U32") (pin "13") (pinfunction "A_13") (pintype "passive"))
    )
    (net (code "144") (name "Net-(U32-A{slash}2)") (class "Default")
      (node (ref "J7") (pin "1") (pinfunction "1_1") (pintype "passive"))
      (node (ref "U32") (pin "7") (pinfunction "A/2_7") (pintype "passive"))
      (node (ref "U33") (pin "1") (pinfunction "1_1") (pintype "passive"))
    )
    (net (code "145") (name "Net-(U32-B)") (class "Default")
      (node (ref "R33") (pin "1") (pinfunction "1_1") (pintype "passive"))
      (node (ref "U32") (pin "12") (pinfunction "B_12") (pintype "passive"))
    )
    (net (code "146") (name "Net-(U32-B{slash}2)") (class "Default")
      (node (ref "J7") (pin "2") (pinfunction "2_2") (pintype "passive"))
      (node (ref "U32") (pin "1") (pinfunction "B/2_1") (pintype "passive"))
      (node (ref "U34") (pin "1") (pinfunction "1_1") (pintype "passive"))
    )
    (net (code "147") (name "Net-(U32-C)") (class "Default")
      (node (ref "R34") (pin "1") (pinfunction "1_1") (pintype "passive"))
      (node (ref "U32") (pin "11") (pinfunction "C_11") (pintype "passive"))
    )
    (net (code "148") (name "Net-(U32-C{slash}2)") (class "Default")
      (node (ref "J7") (pin "3") (pinfunction "3_3") (pintype "passive"))
      (node (ref "U32") (pin "2") (pinfunction "C/2_2") (pintype "passive"))
      (node (ref "U35") (pin "1") (pinfunction "1_1") (pintype "passive"))
    )
    (net (code "149") (name "Net-(U32-D)") (class "Default")
      (node (ref "R35") (pin "1") (pinfunction "1_1") (pintype "passive"))
      (node (ref "U32") (pin "10") (pinfunction "D_10") (pintype "passive"))
    )
    (net (code "150") (name "Net-(U32-D{slash}2)") (class "Default")
      (node (ref "J7") (pin "4") (pinfunction "4_4") (pintype "passive"))
      (node (ref "U32") (pin "6") (pinfunction "D/2_6") (pintype "passive"))
      (node (ref "U36") (pin "1") (pinfunction "1_1") (pintype "passive"))
    )
    (net (code "151") (name "Net-(U32-E)") (class "Default")
      (node (ref "R36") (pin "1") (pinfunction "1_1") (pintype "passive"))
      (node (ref "U32") (pin "9") (pinfunction "E_9") (pintype "passive"))
    )
    (net (code "152") (name "Net-(U32-F)") (class "Default")
      (node (ref "R37") (pin "1") (pinfunction "1_1") (pintype "passive"))
      (node (ref "U32") (pin "15") (pinfunction "F_15") (pintype "passive"))
    )
    (net (code "153") (name "Net-(U32-G)") (class "Default")
      (node (ref "R38") (pin "1") (pinfunction "1_1") (pintype "passive"))
      (node (ref "U32") (pin "14") (pinfunction "G_14") (pintype "passive"))
    )
    (net (code "154") (name "Net-(U41-A)") (class "Default")
      (node (ref "R45") (pin "1") (pinfunction "1_1") (pintype "passive"))
      (node (ref "U41") (pin "13") (pinfunction "A_13") (pintype "passive"))
    )
    (net (code "155") (name "Net-(U41-A{slash}2)") (class "Default")
      (node (ref "J8") (pin "1") (pinfunction "1_1") (pintype "passive"))
      (node (ref "U40") (pin "1") (pinfunction "1_1") (pintype "passive"))
      (node (ref "U41") (pin "7") (pinfunction "A/2_7") (pintype "passive"))
    )
    (net (code "156") (name "Net-(U41-B)") (class "Default")
      (node (ref "R44") (pin "1") (pinfunction "1_1") (pintype "passive"))
      (node (ref "U41") (pin "12") (pinfunction "B_12") (pintype "passive"))
    )
    (net (code "157") (name "Net-(U41-B{slash}2)") (class "Default")
      (node (ref "J8") (pin "2") (pinfunction "2_2") (pintype "passive"))
      (node (ref "U39") (pin "1") (pinfunction "1_1") (pintype "passive"))
      (node (ref "U41") (pin "1") (pinfunction "B/2_1") (pintype "passive"))
    )
    (net (code "158") (name "Net-(U41-C)") (class "Default")
      (node (ref "R43") (pin "1") (pinfunction "1_1") (pintype "passive"))
      (node (ref "U41") (pin "11") (pinfunction "C_11") (pintype "passive"))
    )
    (net (code "159") (name "Net-(U41-C{slash}2)") (class "Default")
      (node (ref "J8") (pin "3") (pinfunction "3_3") (pintype "passive"))
      (node (ref "U38") (pin "1") (pinfunction "1_1") (pintype "passive"))
      (node (ref "U41") (pin "2") (pinfunction "C/2_2") (pintype "passive"))
    )
    (net (code "160") (name "Net-(U41-D)") (class "Default")
      (node (ref "R42") (pin "1") (pinfunction "1_1") (pintype "passive"))
      (node (ref "U41") (pin "10") (pinfunction "D_10") (pintype "passive"))
    )
    (net (code "161") (name "Net-(U41-D{slash}2)") (class "Default")
      (node (ref "J8") (pin "4") (pinfunction "4_4") (pintype "passive"))
      (node (ref "U37") (pin "1") (pinfunction "1_1") (pintype "passive"))
      (node (ref "U41") (pin "6") (pinfunction "D/2_6") (pintype "passive"))
    )
    (net (code "162") (name "Net-(U41-E)") (class "Default")
      (node (ref "R41") (pin "1") (pinfunction "1_1") (pintype "passive"))
      (node (ref "U41") (pin "9") (pinfunction "E_9") (pintype "passive"))
    )
    (net (code "163") (name "Net-(U41-F)") (class "Default")
      (node (ref "R40") (pin "1") (pinfunction "1_1") (pintype "passive"))
      (node (ref "U41") (pin "15") (pinfunction "F_15") (pintype "passive"))
    )
    (net (code "164") (name "Net-(U41-G)") (class "Default")
      (node (ref "R39") (pin "1") (pinfunction "1_1") (pintype "passive"))
      (node (ref "U41") (pin "14") (pinfunction "G_14") (pintype "passive"))
    )
    (net (code "165") (name "VCC") (class "Default")
      (node (ref "C3") (pin "2") (pinfunction "2_2") (pintype "passive"))
      (node (ref "C4") (pin "1") (pinfunction "1_1") (pintype "passive"))
      (node (ref "J10") (pin "1") (pinfunction "1_1") (pintype "passive"))
      (node (ref "J9") (pin "1") (pinfunction "1_1") (pintype "passive"))
      (node (ref "J9") (pin "11") (pinfunction "11_11") (pintype "passive"))
      (node (ref "J9") (pin "3") (pinfunction "3_3") (pintype "passive"))
      (node (ref "J9") (pin "5") (pinfunction "5_5") (pintype "passive"))
      (node (ref "J9") (pin "7") (pinfunction "7_7") (pintype "passive"))
      (node (ref "J9") (pin "9") (pinfunction "9_9") (pintype "passive"))
      (node (ref "R2") (pin "2") (pinfunction "2_2") (pintype "passive"))
      (node (ref "R46") (pin "2") (pinfunction "2_2") (pintype "passive"))
      (node (ref "R47") (pin "2") (pinfunction "2_2") (pintype "passive"))
      (node (ref "R48") (pin "2") (pinfunction "2_2") (pintype "passive"))
      (node (ref "R49") (pin "2") (pinfunction "2_2") (pintype "passive"))
      (node (ref "R50") (pin "2") (pinfunction "2_2") (pintype "passive"))
      (node (ref "R51") (pin "2") (pinfunction "2_2") (pintype "passive"))
      (node (ref "R52") (pin "2") (pinfunction "2_2") (pintype "passive"))
      (node (ref "R53") (pin "2") (pinfunction "2_2") (pintype "passive"))
      (node (ref "SW1") (pin "1") (pinfunction "1_1") (pintype "passive"))
      (node (ref "SW1") (pin "6") (pinfunction "6_6") (pintype "passive"))
      (node (ref "SW2") (pin "1") (pinfunction "1_1") (pintype "passive"))
      (node (ref "SW2") (pin "6") (pinfunction "6_6") (pintype "passive"))
      (node (ref "SW3") (pin "1") (pinfunction "1_1") (pintype "passive"))
      (node (ref "SW3") (pin "6") (pinfunction "6_6") (pintype "passive"))
      (node (ref "SW4") (pin "1") (pinfunction "1_1") (pintype "passive"))
      (node (ref "SW4") (pin "6") (pinfunction "6_6") (pintype "passive"))
      (node (ref "SW5") (pin "1") (pinfunction "1_1") (pintype "passive"))
      (node (ref "SW5") (pin "6") (pinfunction "6_6") (pintype "passive"))
      (node (ref "SW6") (pin "1") (pinfunction "1_1") (pintype "passive"))
      (node (ref "SW6") (pin "6") (pinfunction "6_6") (pintype "passive"))
      (node (ref "SW7") (pin "1") (pinfunction "1_1") (pintype "passive"))
      (node (ref "SW7") (pin "6") (pinfunction "6_6") (pintype "passive"))
      (node (ref "SW8") (pin "1") (pinfunction "1_1") (pintype "passive"))
      (node (ref "SW8") (pin "6") (pinfunction "6_6") (pintype "passive"))
      (node (ref "U1") (pin "4") (pinfunction "Reset_4") (pintype "passive"))
      (node (ref "U1") (pin "8") (pinfunction "VCC_8") (pintype "passive"))
      (node (ref "U12") (pin "16") (pinfunction "VDD_16") (pintype "passive"))
      (node (ref "U12") (pin "3") (pinfunction "LT_3") (pintype "passive"))
      (node (ref "U12") (pin "4") (pinfunction "BT_4") (pintype "passive"))
      (node (ref "U21") (pin "16") (pinfunction "VDD_16") (pintype "passive"))
      (node (ref "U21") (pin "3") (pinfunction "LT_3") (pintype "passive"))
      (node (ref "U21") (pin "4") (pinfunction "BT_4") (pintype "passive"))
      (node (ref "U26") (pin "16") (pinfunction "VDD_16") (pintype "passive"))
      (node (ref "U26") (pin "3") (pinfunction "LT_3") (pintype "passive"))
      (node (ref "U26") (pin "4") (pinfunction "BT_4") (pintype "passive"))
      (node (ref "U27") (pin "16") (pinfunction "VDD_16") (pintype "passive"))
      (node (ref "U27") (pin "3") (pinfunction "LT_3") (pintype "passive"))
      (node (ref "U27") (pin "4") (pinfunction "BT_4") (pintype "passive"))
      (node (ref "U32") (pin "16") (pinfunction "VDD_16") (pintype "passive"))
      (node (ref "U32") (pin "3") (pinfunction "LT_3") (pintype "passive"))
      (node (ref "U32") (pin "4") (pinfunction "BT_4") (pintype "passive"))
      (node (ref "U41") (pin "16") (pinfunction "VDD_16") (pintype "passive"))
      (node (ref "U41") (pin "3") (pinfunction "LT_3") (pintype "passive"))
      (node (ref "U41") (pin "4") (pinfunction "BT_4") (pintype "passive"))
      (node (ref "U42") (pin "1") (pinfunction "1_1") (pintype "passive"))
      (node (ref "U43") (pin "1") (pinfunction "1_1") (pintype "passive"))
      (node (ref "U44") (pin "1") (pinfunction "1_1") (pintype "passive"))
      (node (ref "U45") (pin "1") (pinfunction "1_1") (pintype "passive"))
      (node (ref "U46") (pin "1") (pinfunction "1_1") (pintype "passive"))
      (node (ref "U47") (pin "1") (pinfunction "1_1") (pintype "passive"))
      (node (ref "USB1") (pin "1") (pinfunction "VCC_1") (pintype "passive"))
    )
    (net (code "166") (name "unconnected-(USB1-D+-Pad3)") (class "Default")
      (node (ref "USB1") (pin "3") (pinfunction "D+_3") (pintype "passive+no_connect"))
    )
    (net (code "167") (name "unconnected-(USB1-D--Pad2)") (class "Default")
      (node (ref "USB1") (pin "2") (pinfunction "D-_2") (pintype "passive+no_connect"))
    )
  )
)
